# BMS_25.net
KiCad netlist of a schematic drawn in EAGLE
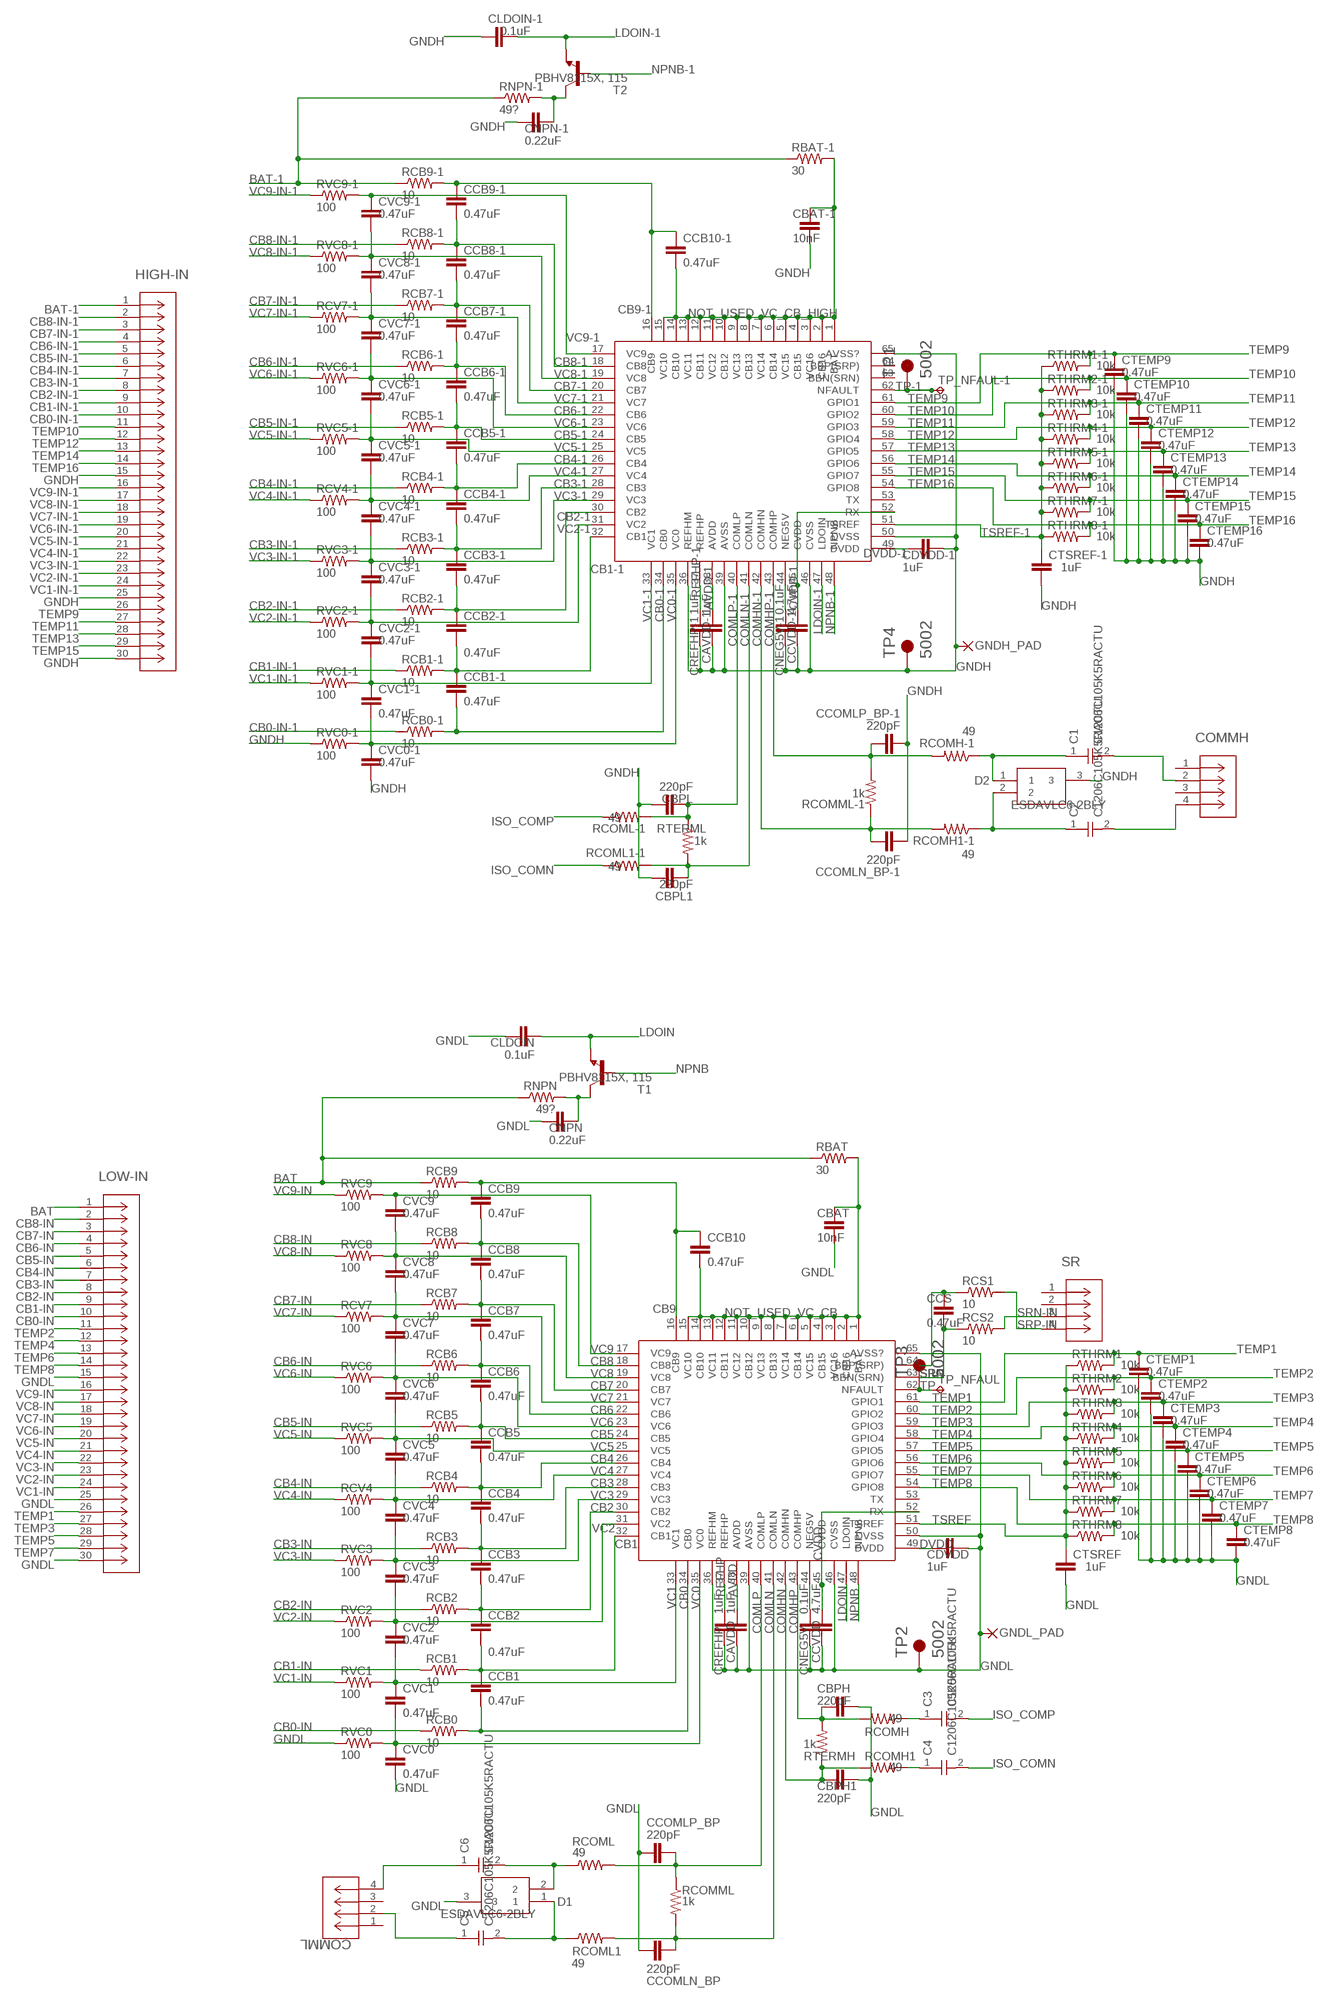
[diagram p0: schematic, sheet 1]

(export (version "E")
  (design (tool "Eeschema 10.0.6"))
  (components
    (comp (ref "C1")
      (value "C1206C105K5RACTU")
      (footprint "eagle-import:CAPC3216X120N")
      (fields (field (name "MF") "KEMET"))
      (libsource (lib "eagle-import") (part "C1206C105K5RACTU"))
    )
    (comp (ref "C2")
      (value "C1206C105K5RACTU")
      (footprint "eagle-import:CAPC3216X120N")
      (fields (field (name "MF") "KEMET"))
      (libsource (lib "eagle-import") (part "C1206C105K5RACTU"))
    )
    (comp (ref "C3")
      (value "C1206C105K5RACTU")
      (footprint "eagle-import:CAPC3216X120N")
      (fields (field (name "MF") "KEMET"))
      (libsource (lib "eagle-import") (part "C1206C105K5RACTU"))
    )
    (comp (ref "C4")
      (value "C1206C105K5RACTU")
      (footprint "eagle-import:CAPC3216X120N")
      (fields (field (name "MF") "KEMET"))
      (libsource (lib "eagle-import") (part "C1206C105K5RACTU"))
    )
    (comp (ref "C5")
      (value "C1206C105K5RACTU")
      (footprint "eagle-import:CAPC3216X120N")
      (fields (field (name "MF") "KEMET"))
      (libsource (lib "eagle-import") (part "C1206C105K5RACTU"))
    )
    (comp (ref "C6")
      (value "C1206C105K5RACTU")
      (footprint "eagle-import:CAPC3216X120N")
      (fields (field (name "MF") "KEMET"))
      (libsource (lib "eagle-import") (part "C1206C105K5RACTU"))
    )
    (comp (ref "CAVDD")
      (value "1uF")
      (footprint "eagle-import:C0603")
      (libsource (lib "eagle-import") (part "CAPACITORC0603"))
    )
    (comp (ref "CAVDD-1")
      (value "1uF")
      (footprint "eagle-import:C0603")
      (libsource (lib "eagle-import") (part "CAPACITORC0603"))
    )
    (comp (ref "CBAT")
      (value "10nF")
      (footprint "eagle-import:C0603")
      (libsource (lib "eagle-import") (part "CAPACITORC0603"))
    )
    (comp (ref "CBAT-1")
      (value "10nF")
      (footprint "eagle-import:C0603")
      (libsource (lib "eagle-import") (part "CAPACITORC0603"))
    )
    (comp (ref "CBPH")
      (value "220pF")
      (footprint "eagle-import:C0603")
      (libsource (lib "eagle-import") (part "CAPACITORC0603"))
    )
    (comp (ref "CBPH1")
      (value "220pF")
      (footprint "eagle-import:C0603")
      (libsource (lib "eagle-import") (part "CAPACITORC0603"))
    )
    (comp (ref "CBPL")
      (value "220pF")
      (footprint "eagle-import:C0603")
      (libsource (lib "eagle-import") (part "CAPACITORC0603"))
    )
    (comp (ref "CBPL1")
      (value "220pF")
      (footprint "eagle-import:C0603")
      (libsource (lib "eagle-import") (part "CAPACITORC0603"))
    )
    (comp (ref "CCB1")
      (value "0.47uF")
      (footprint "eagle-import:C0603")
      (libsource (lib "eagle-import") (part "CAPACITORC0603"))
    )
    (comp (ref "CCB1-1")
      (value "0.47uF")
      (footprint "eagle-import:C0603")
      (libsource (lib "eagle-import") (part "CAPACITORC0603"))
    )
    (comp (ref "CCB2")
      (value "0.47uF")
      (footprint "eagle-import:C0603")
      (libsource (lib "eagle-import") (part "CAPACITORC0603"))
    )
    (comp (ref "CCB2-1")
      (value "0.47uF")
      (footprint "eagle-import:C0603")
      (libsource (lib "eagle-import") (part "CAPACITORC0603"))
    )
    (comp (ref "CCB3")
      (value "0.47uF")
      (footprint "eagle-import:C0603")
      (libsource (lib "eagle-import") (part "CAPACITORC0603"))
    )
    (comp (ref "CCB3-1")
      (value "0.47uF")
      (footprint "eagle-import:C0603")
      (libsource (lib "eagle-import") (part "CAPACITORC0603"))
    )
    (comp (ref "CCB4")
      (value "0.47uF")
      (footprint "eagle-import:C0603")
      (libsource (lib "eagle-import") (part "CAPACITORC0603"))
    )
    (comp (ref "CCB4-1")
      (value "0.47uF")
      (footprint "eagle-import:C0603")
      (libsource (lib "eagle-import") (part "CAPACITORC0603"))
    )
    (comp (ref "CCB5")
      (value "0.47uF")
      (footprint "eagle-import:C0603")
      (libsource (lib "eagle-import") (part "CAPACITORC0603"))
    )
    (comp (ref "CCB5-1")
      (value "0.47uF")
      (footprint "eagle-import:C0603")
      (libsource (lib "eagle-import") (part "CAPACITORC0603"))
    )
    (comp (ref "CCB6")
      (value "0.47uF")
      (footprint "eagle-import:C0603")
      (libsource (lib "eagle-import") (part "CAPACITORC0603"))
    )
    (comp (ref "CCB6-1")
      (value "0.47uF")
      (footprint "eagle-import:C0603")
      (libsource (lib "eagle-import") (part "CAPACITORC0603"))
    )
    (comp (ref "CCB7")
      (value "0.47uF")
      (footprint "eagle-import:C0603")
      (libsource (lib "eagle-import") (part "CAPACITORC0603"))
    )
    (comp (ref "CCB7-1")
      (value "0.47uF")
      (footprint "eagle-import:C0603")
      (libsource (lib "eagle-import") (part "CAPACITORC0603"))
    )
    (comp (ref "CCB8")
      (value "0.47uF")
      (footprint "eagle-import:C0603")
      (libsource (lib "eagle-import") (part "CAPACITORC0603"))
    )
    (comp (ref "CCB8-1")
      (value "0.47uF")
      (footprint "eagle-import:C0603")
      (libsource (lib "eagle-import") (part "CAPACITORC0603"))
    )
    (comp (ref "CCB9")
      (value "0.47uF")
      (footprint "eagle-import:C0603")
      (libsource (lib "eagle-import") (part "CAPACITORC0603"))
    )
    (comp (ref "CCB9-1")
      (value "0.47uF")
      (footprint "eagle-import:C0603")
      (libsource (lib "eagle-import") (part "CAPACITORC0603"))
    )
    (comp (ref "CCB10")
      (value "0.47uF")
      (footprint "eagle-import:C0603")
      (libsource (lib "eagle-import") (part "CAPACITORC0603"))
    )
    (comp (ref "CCB10-1")
      (value "0.47uF")
      (footprint "eagle-import:C0603")
      (libsource (lib "eagle-import") (part "CAPACITORC0603"))
    )
    (comp (ref "CCOMLN_BP")
      (value "220pF")
      (footprint "eagle-import:C0603")
      (libsource (lib "eagle-import") (part "CAPACITORC0603"))
    )
    (comp (ref "CCOMLN_BP-1")
      (value "220pF")
      (footprint "eagle-import:C0603")
      (libsource (lib "eagle-import") (part "CAPACITORC0603"))
    )
    (comp (ref "CCOMLP_BP")
      (value "220pF")
      (footprint "eagle-import:C0603")
      (libsource (lib "eagle-import") (part "CAPACITORC0603"))
    )
    (comp (ref "CCOMLP_BP-1")
      (value "220pF")
      (footprint "eagle-import:C0603")
      (libsource (lib "eagle-import") (part "CAPACITORC0603"))
    )
    (comp (ref "CCS")
      (value "0.47uF")
      (footprint "eagle-import:C0603")
      (libsource (lib "eagle-import") (part "CAPACITORC0603"))
    )
    (comp (ref "CCVDD")
      (value "4.7uF")
      (footprint "eagle-import:C0603")
      (libsource (lib "eagle-import") (part "CAPACITORC0603"))
    )
    (comp (ref "CCVDD-1")
      (value "4.7uF")
      (footprint "eagle-import:C0603")
      (libsource (lib "eagle-import") (part "CAPACITORC0603"))
    )
    (comp (ref "CDVDD")
      (value "1uF")
      (footprint "eagle-import:C0603")
      (libsource (lib "eagle-import") (part "CAPACITORC0603"))
    )
    (comp (ref "CDVDD-1")
      (value "1uF")
      (footprint "eagle-import:C0603")
      (libsource (lib "eagle-import") (part "CAPACITORC0603"))
    )
    (comp (ref "CLDOIN")
      (value "0.1uF")
      (footprint "eagle-import:C0603")
      (libsource (lib "eagle-import") (part "CAPACITORC0603"))
    )
    (comp (ref "CLDOIN-1")
      (value "0.1uF")
      (footprint "eagle-import:C0603")
      (libsource (lib "eagle-import") (part "CAPACITORC0603"))
    )
    (comp (ref "CNEG5V")
      (value "0.1uF")
      (footprint "eagle-import:C0603")
      (libsource (lib "eagle-import") (part "CAPACITORC0603"))
    )
    (comp (ref "CNEG5V-1")
      (value "0.1uF")
      (footprint "eagle-import:C0603")
      (libsource (lib "eagle-import") (part "CAPACITORC0603"))
    )
    (comp (ref "CNPN")
      (value "0.22uF")
      (footprint "eagle-import:C0603")
      (libsource (lib "eagle-import") (part "CAPACITORC0603"))
    )
    (comp (ref "CNPN-1")
      (value "0.22uF")
      (footprint "eagle-import:C0603")
      (libsource (lib "eagle-import") (part "CAPACITORC0603"))
    )
    (comp (ref "COMMH")
      (value "DF11-4DP-2DSA(24)")
      (footprint "eagle-import:CON4_2X2_UF_DF11_HIR")
      (fields (field (name "COPYRIGHT") "Copyright (C) 2023 Ultra Librarian. All rights reserved."))
      (libsource (lib "eagle-import") (part "DF11-4DP-2DSA(24)"))
    )
    (comp (ref "COMML")
      (value "DF11-4DP-2DSA(24)")
      (footprint "eagle-import:CON4_2X2_UF_DF11_HIR")
      (fields (field (name "COPYRIGHT") "Copyright (C) 2023 Ultra Librarian. All rights reserved."))
      (libsource (lib "eagle-import") (part "DF11-4DP-2DSA(24)"))
    )
    (comp (ref "CREFHP")
      (value "1uF")
      (footprint "eagle-import:C0603")
      (libsource (lib "eagle-import") (part "CAPACITORC0603"))
    )
    (comp (ref "CREFHP-1")
      (value "1uF")
      (footprint "eagle-import:C0603")
      (libsource (lib "eagle-import") (part "CAPACITORC0603"))
    )
    (comp (ref "CTEMP1")
      (value "0.47uF")
      (footprint "eagle-import:C0603")
      (libsource (lib "eagle-import") (part "CAPACITORC0603"))
    )
    (comp (ref "CTEMP2")
      (value "0.47uF")
      (footprint "eagle-import:C0603")
      (libsource (lib "eagle-import") (part "CAPACITORC0603"))
    )
    (comp (ref "CTEMP3")
      (value "0.47uF")
      (footprint "eagle-import:C0603")
      (libsource (lib "eagle-import") (part "CAPACITORC0603"))
    )
    (comp (ref "CTEMP4")
      (value "0.47uF")
      (footprint "eagle-import:C0603")
      (libsource (lib "eagle-import") (part "CAPACITORC0603"))
    )
    (comp (ref "CTEMP5")
      (value "0.47uF")
      (footprint "eagle-import:C0603")
      (libsource (lib "eagle-import") (part "CAPACITORC0603"))
    )
    (comp (ref "CTEMP6")
      (value "0.47uF")
      (footprint "eagle-import:C0603")
      (libsource (lib "eagle-import") (part "CAPACITORC0603"))
    )
    (comp (ref "CTEMP7")
      (value "0.47uF")
      (footprint "eagle-import:C0603")
      (libsource (lib "eagle-import") (part "CAPACITORC0603"))
    )
    (comp (ref "CTEMP8")
      (value "0.47uF")
      (footprint "eagle-import:C0603")
      (libsource (lib "eagle-import") (part "CAPACITORC0603"))
    )
    (comp (ref "CTEMP9")
      (value "0.47uF")
      (footprint "eagle-import:C0603")
      (libsource (lib "eagle-import") (part "CAPACITORC0603"))
    )
    (comp (ref "CTEMP10")
      (value "0.47uF")
      (footprint "eagle-import:C0603")
      (libsource (lib "eagle-import") (part "CAPACITORC0603"))
    )
    (comp (ref "CTEMP11")
      (value "0.47uF")
      (footprint "eagle-import:C0603")
      (libsource (lib "eagle-import") (part "CAPACITORC0603"))
    )
    (comp (ref "CTEMP12")
      (value "0.47uF")
      (footprint "eagle-import:C0603")
      (libsource (lib "eagle-import") (part "CAPACITORC0603"))
    )
    (comp (ref "CTEMP13")
      (value "0.47uF")
      (footprint "eagle-import:C0603")
      (libsource (lib "eagle-import") (part "CAPACITORC0603"))
    )
    (comp (ref "CTEMP14")
      (value "0.47uF")
      (footprint "eagle-import:C0603")
      (libsource (lib "eagle-import") (part "CAPACITORC0603"))
    )
    (comp (ref "CTEMP15")
      (value "0.47uF")
      (footprint "eagle-import:C0603")
      (libsource (lib "eagle-import") (part "CAPACITORC0603"))
    )
    (comp (ref "CTEMP16")
      (value "0.47uF")
      (footprint "eagle-import:C0603")
      (libsource (lib "eagle-import") (part "CAPACITORC0603"))
    )
    (comp (ref "CTSREF")
      (value "1uF")
      (footprint "eagle-import:C0603")
      (libsource (lib "eagle-import") (part "CAPACITORC0603"))
    )
    (comp (ref "CTSREF-1")
      (value "1uF")
      (footprint "eagle-import:C0603")
      (libsource (lib "eagle-import") (part "CAPACITORC0603"))
    )
    (comp (ref "CVC0")
      (value "0.47uF")
      (footprint "eagle-import:C0603")
      (libsource (lib "eagle-import") (part "CAPACITORC0603"))
    )
    (comp (ref "CVC0-1")
      (value "0.47uF")
      (footprint "eagle-import:C0603")
      (libsource (lib "eagle-import") (part "CAPACITORC0603"))
    )
    (comp (ref "CVC1")
      (value "0.47uF")
      (footprint "eagle-import:C0603")
      (libsource (lib "eagle-import") (part "CAPACITORC0603"))
    )
    (comp (ref "CVC1-1")
      (value "0.47uF")
      (footprint "eagle-import:C0603")
      (libsource (lib "eagle-import") (part "CAPACITORC0603"))
    )
    (comp (ref "CVC2")
      (value "0.47uF")
      (footprint "eagle-import:C0603")
      (libsource (lib "eagle-import") (part "CAPACITORC0603"))
    )
    (comp (ref "CVC2-1")
      (value "0.47uF")
      (footprint "eagle-import:C0603")
      (libsource (lib "eagle-import") (part "CAPACITORC0603"))
    )
    (comp (ref "CVC3")
      (value "0.47uF")
      (footprint "eagle-import:C0603")
      (libsource (lib "eagle-import") (part "CAPACITORC0603"))
    )
    (comp (ref "CVC3-1")
      (value "0.47uF")
      (footprint "eagle-import:C0603")
      (libsource (lib "eagle-import") (part "CAPACITORC0603"))
    )
    (comp (ref "CVC4")
      (value "0.47uF")
      (footprint "eagle-import:C0603")
      (libsource (lib "eagle-import") (part "CAPACITORC0603"))
    )
    (comp (ref "CVC4-1")
      (value "0.47uF")
      (footprint "eagle-import:C0603")
      (libsource (lib "eagle-import") (part "CAPACITORC0603"))
    )
    (comp (ref "CVC5")
      (value "0.47uF")
      (footprint "eagle-import:C0603")
      (libsource (lib "eagle-import") (part "CAPACITORC0603"))
    )
    (comp (ref "CVC5-1")
      (value "0.47uF")
      (footprint "eagle-import:C0603")
      (libsource (lib "eagle-import") (part "CAPACITORC0603"))
    )
    (comp (ref "CVC6")
      (value "0.47uF")
      (footprint "eagle-import:C0603")
      (libsource (lib "eagle-import") (part "CAPACITORC0603"))
    )
    (comp (ref "CVC6-1")
      (value "0.47uF")
      (footprint "eagle-import:C0603")
      (libsource (lib "eagle-import") (part "CAPACITORC0603"))
    )
    (comp (ref "CVC7")
      (value "0.47uF")
      (footprint "eagle-import:C0603")
      (libsource (lib "eagle-import") (part "CAPACITORC0603"))
    )
    (comp (ref "CVC7-1")
      (value "0.47uF")
      (footprint "eagle-import:C0603")
      (libsource (lib "eagle-import") (part "CAPACITORC0603"))
    )
    (comp (ref "CVC8")
      (value "0.47uF")
      (footprint "eagle-import:C0603")
      (libsource (lib "eagle-import") (part "CAPACITORC0603"))
    )
    (comp (ref "CVC8-1")
      (value "0.47uF")
      (footprint "eagle-import:C0603")
      (libsource (lib "eagle-import") (part "CAPACITORC0603"))
    )
    (comp (ref "CVC9")
      (value "0.47uF")
      (footprint "eagle-import:C0603")
      (libsource (lib "eagle-import") (part "CAPACITORC0603"))
    )
    (comp (ref "CVC9-1")
      (value "0.47uF")
      (footprint "eagle-import:C0603")
      (libsource (lib "eagle-import") (part "CAPACITORC0603"))
    )
    (comp (ref "D1")
      (value "ESDAVLC6-2BLY")
      (footprint "eagle-import:SOT95P255X150-3N")
      (fields (field (name "MOUSER_PART_NUMBER") "511-ESDAVLC6-2BLY"))
      (libsource (lib "eagle-import") (part "ESDAVLC6-2BLY"))
    )
    (comp (ref "D2")
      (value "ESDAVLC6-2BLY")
      (footprint "eagle-import:SOT95P255X150-3N")
      (fields (field (name "MOUSER_PART_NUMBER") "511-ESDAVLC6-2BLY"))
      (libsource (lib "eagle-import") (part "ESDAVLC6-2BLY"))
    )
    (comp (ref "GNDH_PAD")
      (value "SMD2")
      (footprint "eagle-import:SMD1,27-2,54")
      (libsource (lib "eagle-import") (part "SMD2"))
    )
    (comp (ref "GNDL_PAD")
      (value "SMD2")
      (footprint "eagle-import:SMD1,27-2,54")
      (libsource (lib "eagle-import") (part "SMD2"))
    )
    (comp (ref "HIGH-IN")
      (value "87606-315LF")
      (footprint "eagle-import:87606-315LF_AMP")
      (fields (field (name "COPYRIGHT") "Copyright (C) 2024 Ultra Librarian. All rights reserved."))
      (libsource (lib "eagle-import") (part "87606-315LF"))
    )
    (comp (ref "IC1")
      (value "PBQ79656PAPTQ1")
      (footprint "eagle-import:QFP50P1200X1200X120-65N")
      (libsource (lib "eagle-import") (part "PBQ79656PAPTQ1"))
    )
    (comp (ref "IC2")
      (value "PBQ79656PAPTQ1")
      (footprint "eagle-import:QFP50P1200X1200X120-65N")
      (libsource (lib "eagle-import") (part "PBQ79656PAPTQ1"))
    )
    (comp (ref "LOW-IN")
      (value "87606-315LF")
      (footprint "eagle-import:87606-315LF_AMP")
      (fields (field (name "COPYRIGHT") "Copyright (C) 2024 Ultra Librarian. All rights reserved."))
      (libsource (lib "eagle-import") (part "87606-315LF"))
    )
    (comp (ref "RBAT")
      (value "30")
      (footprint "eagle-import:R0603")
      (libsource (lib "eagle-import") (part "RESISTORR0603"))
    )
    (comp (ref "RBAT-1")
      (value "30")
      (footprint "eagle-import:R0603")
      (libsource (lib "eagle-import") (part "RESISTORR0603"))
    )
    (comp (ref "RCB0")
      (value "10")
      (footprint "eagle-import:R2010")
      (libsource (lib "eagle-import") (part "R-US_R2010"))
    )
    (comp (ref "RCB0-1")
      (value "10")
      (footprint "eagle-import:R2010")
      (libsource (lib "eagle-import") (part "R-US_R2010"))
    )
    (comp (ref "RCB1")
      (value "10")
      (footprint "eagle-import:R2010")
      (libsource (lib "eagle-import") (part "R-US_R2010"))
    )
    (comp (ref "RCB1-1")
      (value "10")
      (footprint "eagle-import:R2010")
      (libsource (lib "eagle-import") (part "R-US_R2010"))
    )
    (comp (ref "RCB2")
      (value "10")
      (footprint "eagle-import:R2010")
      (libsource (lib "eagle-import") (part "R-US_R2010"))
    )
    (comp (ref "RCB2-1")
      (value "10")
      (footprint "eagle-import:R2010")
      (libsource (lib "eagle-import") (part "R-US_R2010"))
    )
    (comp (ref "RCB3")
      (value "10")
      (footprint "eagle-import:R2010")
      (libsource (lib "eagle-import") (part "R-US_R2010"))
    )
    (comp (ref "RCB3-1")
      (value "10")
      (footprint "eagle-import:R2010")
      (libsource (lib "eagle-import") (part "R-US_R2010"))
    )
    (comp (ref "RCB4")
      (value "10")
      (footprint "eagle-import:R2010")
      (libsource (lib "eagle-import") (part "R-US_R2010"))
    )
    (comp (ref "RCB4-1")
      (value "10")
      (footprint "eagle-import:R2010")
      (libsource (lib "eagle-import") (part "R-US_R2010"))
    )
    (comp (ref "RCB5")
      (value "10")
      (footprint "eagle-import:R2010")
      (libsource (lib "eagle-import") (part "R-US_R2010"))
    )
    (comp (ref "RCB5-1")
      (value "10")
      (footprint "eagle-import:R2010")
      (libsource (lib "eagle-import") (part "R-US_R2010"))
    )
    (comp (ref "RCB6")
      (value "10")
      (footprint "eagle-import:R2010")
      (libsource (lib "eagle-import") (part "R-US_R2010"))
    )
    (comp (ref "RCB6-1")
      (value "10")
      (footprint "eagle-import:R2010")
      (libsource (lib "eagle-import") (part "R-US_R2010"))
    )
    (comp (ref "RCB7")
      (value "10")
      (footprint "eagle-import:R2010")
      (libsource (lib "eagle-import") (part "R-US_R2010"))
    )
    (comp (ref "RCB7-1")
      (value "10")
      (footprint "eagle-import:R2010")
      (libsource (lib "eagle-import") (part "R-US_R2010"))
    )
    (comp (ref "RCB8")
      (value "10")
      (footprint "eagle-import:R2010")
      (libsource (lib "eagle-import") (part "R-US_R2010"))
    )
    (comp (ref "RCB8-1")
      (value "10")
      (footprint "eagle-import:R2010")
      (libsource (lib "eagle-import") (part "R-US_R2010"))
    )
    (comp (ref "RCB9")
      (value "10")
      (footprint "eagle-import:R2010")
      (libsource (lib "eagle-import") (part "R-US_R2010"))
    )
    (comp (ref "RCB9-1")
      (value "10")
      (footprint "eagle-import:R2010")
      (libsource (lib "eagle-import") (part "R-US_R2010"))
    )
    (comp (ref "RCOMH")
      (value "49")
      (footprint "eagle-import:R0603")
      (libsource (lib "eagle-import") (part "RESISTORR0603"))
    )
    (comp (ref "RCOMH-1")
      (value "49")
      (footprint "eagle-import:R0603")
      (libsource (lib "eagle-import") (part "RESISTORR0603"))
    )
    (comp (ref "RCOMH1")
      (value "49")
      (footprint "eagle-import:R0603")
      (libsource (lib "eagle-import") (part "RESISTORR0603"))
    )
    (comp (ref "RCOMH1-1")
      (value "49")
      (footprint "eagle-import:R0603")
      (libsource (lib "eagle-import") (part "RESISTORR0603"))
    )
    (comp (ref "RCOML")
      (value "49")
      (footprint "eagle-import:R0603")
      (libsource (lib "eagle-import") (part "RESISTORR0603"))
    )
    (comp (ref "RCOML-1")
      (value "49")
      (footprint "eagle-import:R0603")
      (libsource (lib "eagle-import") (part "RESISTORR0603"))
    )
    (comp (ref "RCOML1")
      (value "49")
      (footprint "eagle-import:R0603")
      (libsource (lib "eagle-import") (part "RESISTORR0603"))
    )
    (comp (ref "RCOML1-1")
      (value "49")
      (footprint "eagle-import:R0603")
      (libsource (lib "eagle-import") (part "RESISTORR0603"))
    )
    (comp (ref "RCOMML")
      (value "1k")
      (footprint "eagle-import:R0603")
      (libsource (lib "eagle-import") (part "RESISTORR0603"))
    )
    (comp (ref "RCOMML-1")
      (value "1k")
      (footprint "eagle-import:R0603")
      (libsource (lib "eagle-import") (part "RESISTORR0603"))
    )
    (comp (ref "RCS1")
      (value "10")
      (footprint "eagle-import:R0603")
      (libsource (lib "eagle-import") (part "RESISTORR0603"))
    )
    (comp (ref "RCS2")
      (value "10")
      (footprint "eagle-import:R0603")
      (libsource (lib "eagle-import") (part "RESISTORR0603"))
    )
    (comp (ref "RCV4")
      (value "100")
      (footprint "eagle-import:R0603")
      (libsource (lib "eagle-import") (part "RESISTORR0603"))
    )
    (comp (ref "RCV4-1")
      (value "100")
      (footprint "eagle-import:R0603")
      (libsource (lib "eagle-import") (part "RESISTORR0603"))
    )
    (comp (ref "RCV7")
      (value "100")
      (footprint "eagle-import:R0603")
      (libsource (lib "eagle-import") (part "RESISTORR0603"))
    )
    (comp (ref "RCV7-1")
      (value "100")
      (footprint "eagle-import:R0603")
      (libsource (lib "eagle-import") (part "RESISTORR0603"))
    )
    (comp (ref "RNPN")
      (value "49?")
      (footprint "eagle-import:R0603")
      (libsource (lib "eagle-import") (part "RESISTORR0603"))
    )
    (comp (ref "RNPN-1")
      (value "49?")
      (footprint "eagle-import:R0603")
      (libsource (lib "eagle-import") (part "RESISTORR0603"))
    )
    (comp (ref "RTERMH")
      (value "1k")
      (footprint "eagle-import:R0603")
      (libsource (lib "eagle-import") (part "RESISTORR0603"))
    )
    (comp (ref "RTERML")
      (value "1k")
      (footprint "eagle-import:R0603")
      (libsource (lib "eagle-import") (part "RESISTORR0603"))
    )
    (comp (ref "RTHRM1")
      (value "10k")
      (footprint "eagle-import:R0603")
      (libsource (lib "eagle-import") (part "RESISTORR0603"))
    )
    (comp (ref "RTHRM1-1")
      (value "10k")
      (footprint "eagle-import:R0603")
      (libsource (lib "eagle-import") (part "RESISTORR0603"))
    )
    (comp (ref "RTHRM2")
      (value "10k")
      (footprint "eagle-import:R0603")
      (libsource (lib "eagle-import") (part "RESISTORR0603"))
    )
    (comp (ref "RTHRM2-1")
      (value "10k")
      (footprint "eagle-import:R0603")
      (libsource (lib "eagle-import") (part "RESISTORR0603"))
    )
    (comp (ref "RTHRM3")
      (value "10k")
      (footprint "eagle-import:R0603")
      (libsource (lib "eagle-import") (part "RESISTORR0603"))
    )
    (comp (ref "RTHRM3-1")
      (value "10k")
      (footprint "eagle-import:R0603")
      (libsource (lib "eagle-import") (part "RESISTORR0603"))
    )
    (comp (ref "RTHRM4")
      (value "10k")
      (footprint "eagle-import:R0603")
      (libsource (lib "eagle-import") (part "RESISTORR0603"))
    )
    (comp (ref "RTHRM4-1")
      (value "10k")
      (footprint "eagle-import:R0603")
      (libsource (lib "eagle-import") (part "RESISTORR0603"))
    )
    (comp (ref "RTHRM5")
      (value "10k")
      (footprint "eagle-import:R0603")
      (libsource (lib "eagle-import") (part "RESISTORR0603"))
    )
    (comp (ref "RTHRM5-1")
      (value "10k")
      (footprint "eagle-import:R0603")
      (libsource (lib "eagle-import") (part "RESISTORR0603"))
    )
    (comp (ref "RTHRM6")
      (value "10k")
      (footprint "eagle-import:R0603")
      (libsource (lib "eagle-import") (part "RESISTORR0603"))
    )
    (comp (ref "RTHRM6-1")
      (value "10k")
      (footprint "eagle-import:R0603")
      (libsource (lib "eagle-import") (part "RESISTORR0603"))
    )
    (comp (ref "RTHRM7")
      (value "10k")
      (footprint "eagle-import:R0603")
      (libsource (lib "eagle-import") (part "RESISTORR0603"))
    )
    (comp (ref "RTHRM7-1")
      (value "10k")
      (footprint "eagle-import:R0603")
      (libsource (lib "eagle-import") (part "RESISTORR0603"))
    )
    (comp (ref "RTHRM8")
      (value "10k")
      (footprint "eagle-import:R0603")
      (libsource (lib "eagle-import") (part "RESISTORR0603"))
    )
    (comp (ref "RTHRM8-1")
      (value "10k")
      (footprint "eagle-import:R0603")
      (libsource (lib "eagle-import") (part "RESISTORR0603"))
    )
    (comp (ref "RVC0")
      (value "100")
      (footprint "eagle-import:R0603")
      (libsource (lib "eagle-import") (part "RESISTORR0603"))
    )
    (comp (ref "RVC0-1")
      (value "100")
      (footprint "eagle-import:R0603")
      (libsource (lib "eagle-import") (part "RESISTORR0603"))
    )
    (comp (ref "RVC1")
      (value "100")
      (footprint "eagle-import:R0603")
      (libsource (lib "eagle-import") (part "RESISTORR0603"))
    )
    (comp (ref "RVC1-1")
      (value "100")
      (footprint "eagle-import:R0603")
      (libsource (lib "eagle-import") (part "RESISTORR0603"))
    )
    (comp (ref "RVC2")
      (value "100")
      (footprint "eagle-import:R0603")
      (libsource (lib "eagle-import") (part "RESISTORR0603"))
    )
    (comp (ref "RVC2-1")
      (value "100")
      (footprint "eagle-import:R0603")
      (libsource (lib "eagle-import") (part "RESISTORR0603"))
    )
    (comp (ref "RVC3")
      (value "100")
      (footprint "eagle-import:R0603")
      (libsource (lib "eagle-import") (part "RESISTORR0603"))
    )
    (comp (ref "RVC3-1")
      (value "100")
      (footprint "eagle-import:R0603")
      (libsource (lib "eagle-import") (part "RESISTORR0603"))
    )
    (comp (ref "RVC5")
      (value "100")
      (footprint "eagle-import:R0603")
      (libsource (lib "eagle-import") (part "RESISTORR0603"))
    )
    (comp (ref "RVC5-1")
      (value "100")
      (footprint "eagle-import:R0603")
      (libsource (lib "eagle-import") (part "RESISTORR0603"))
    )
    (comp (ref "RVC6")
      (value "100")
      (footprint "eagle-import:R0603")
      (libsource (lib "eagle-import") (part "RESISTORR0603"))
    )
    (comp (ref "RVC6-1")
      (value "100")
      (footprint "eagle-import:R0603")
      (libsource (lib "eagle-import") (part "RESISTORR0603"))
    )
    (comp (ref "RVC8")
      (value "100")
      (footprint "eagle-import:R0603")
      (libsource (lib "eagle-import") (part "RESISTORR0603"))
    )
    (comp (ref "RVC8-1")
      (value "100")
      (footprint "eagle-import:R0603")
      (libsource (lib "eagle-import") (part "RESISTORR0603"))
    )
    (comp (ref "RVC9")
      (value "100")
      (footprint "eagle-import:R0603")
      (libsource (lib "eagle-import") (part "RESISTORR0603"))
    )
    (comp (ref "RVC9-1")
      (value "100")
      (footprint "eagle-import:R0603")
      (libsource (lib "eagle-import") (part "RESISTORR0603"))
    )
    (comp (ref "SR")
      (value "DF11-4DP-2DSA(24)")
      (footprint "eagle-import:CON4_2X2_UF_DF11_HIR")
      (fields (field (name "COPYRIGHT") "Copyright (C) 2023 Ultra Librarian. All rights reserved."))
      (libsource (lib "eagle-import") (part "DF11-4DP-2DSA(24)"))
    )
    (comp (ref "T1")
      (value "PBHV8115X, 115")
      (footprint "eagle-import:SOT89-BCE")
      (libsource (lib "eagle-import") (part "-NPN-SOT89-BCEBC868"))
    )
    (comp (ref "T2")
      (value "PBHV8115X, 115")
      (footprint "eagle-import:SOT89-BCE")
      (libsource (lib "eagle-import") (part "-NPN-SOT89-BCEBC868"))
    )
    (comp (ref "TP1")
      (value "5002")
      (footprint "eagle-import:KEYSTONE_5002")
      (fields (field (name "MANUFACTURER") "Keystone"))
      (libsource (lib "eagle-import") (part "5002"))
    )
    (comp (ref "TP2")
      (value "5002")
      (footprint "eagle-import:KEYSTONE_5002")
      (fields (field (name "MANUFACTURER") "Keystone"))
      (libsource (lib "eagle-import") (part "5002"))
    )
    (comp (ref "TP3")
      (value "5002")
      (footprint "eagle-import:KEYSTONE_5002")
      (fields (field (name "MANUFACTURER") "Keystone"))
      (libsource (lib "eagle-import") (part "5002"))
    )
    (comp (ref "TP4")
      (value "5002")
      (footprint "eagle-import:KEYSTONE_5002")
      (fields (field (name "MANUFACTURER") "Keystone"))
      (libsource (lib "eagle-import") (part "5002"))
    )
    (comp (ref "TP_NFAUL")
      (value "TPB2,54")
      (footprint "eagle-import:B2,54")
      (libsource (lib "eagle-import") (part "TPB2,54"))
    )
    (comp (ref "TP_NFAUL-1")
      (value "TPB2,54")
      (footprint "eagle-import:B2,54")
      (libsource (lib "eagle-import") (part "TPB2,54"))
    )
  )
  (nets
    (net (code "1") (name "/AVDD") (class "Default")
      (node (ref "CAVDD") (pin "1") (pinfunction "1_1") (pintype "passive"))
      (node (ref "IC2") (pin "38") (pinfunction "AVDD_38") (pintype "bidirectional"))
    )
    (net (code "2") (name "/AVDD-1") (class "Default")
      (node (ref "CAVDD-1") (pin "1") (pinfunction "1_1") (pintype "passive"))
      (node (ref "IC1") (pin "38") (pinfunction "AVDD_38") (pintype "bidirectional"))
    )
    (net (code "3") (name "/BAT") (class "Default")
      (node (ref "LOW-IN") (pin "1") (pinfunction "1_1") (pintype "passive"))
      (node (ref "RBAT") (pin "1") (pinfunction "1_1") (pintype "passive"))
      (node (ref "RCB9") (pin "1") (pinfunction "1_1") (pintype "passive"))
      (node (ref "RNPN") (pin "1") (pinfunction "1_1") (pintype "passive"))
    )
    (net (code "4") (name "/BAT-1") (class "Default")
      (node (ref "HIGH-IN") (pin "1") (pinfunction "1_1") (pintype "passive"))
      (node (ref "RBAT-1") (pin "1") (pinfunction "1_1") (pintype "passive"))
      (node (ref "RCB9-1") (pin "1") (pinfunction "1_1") (pintype "passive"))
      (node (ref "RNPN-1") (pin "1") (pinfunction "1_1") (pintype "passive"))
    )
    (net (code "5") (name "/CB0") (class "Default")
      (node (ref "CCB1") (pin "2") (pinfunction "2_2") (pintype "passive"))
      (node (ref "IC2") (pin "34") (pinfunction "CB0_34") (pintype "bidirectional"))
      (node (ref "RCB0") (pin "2") (pinfunction "2_2") (pintype "passive"))
    )
    (net (code "6") (name "/CB0-1") (class "Default")
      (node (ref "CCB1-1") (pin "2") (pinfunction "2_2") (pintype "passive"))
      (node (ref "IC1") (pin "34") (pinfunction "CB0_34") (pintype "bidirectional"))
      (node (ref "RCB0-1") (pin "2") (pinfunction "2_2") (pintype "passive"))
    )
    (net (code "7") (name "/CB0-IN") (class "Default")
      (node (ref "LOW-IN") (pin "10") (pinfunction "10_10") (pintype "passive"))
      (node (ref "RCB0") (pin "1") (pinfunction "1_1") (pintype "passive"))
    )
    (net (code "8") (name "/CB0-IN-1") (class "Default")
      (node (ref "HIGH-IN") (pin "10") (pinfunction "10_10") (pintype "passive"))
      (node (ref "RCB0-1") (pin "1") (pinfunction "1_1") (pintype "passive"))
    )
    (net (code "9") (name "/CB1") (class "Default")
      (node (ref "CCB1") (pin "1") (pinfunction "1_1") (pintype "passive"))
      (node (ref "CCB2") (pin "2") (pinfunction "2_2") (pintype "passive"))
      (node (ref "IC2") (pin "32") (pinfunction "CB1_32") (pintype "bidirectional"))
      (node (ref "RCB1") (pin "2") (pinfunction "2_2") (pintype "passive"))
    )
    (net (code "10") (name "/CB1-1") (class "Default")
      (node (ref "CCB1-1") (pin "1") (pinfunction "1_1") (pintype "passive"))
      (node (ref "CCB2-1") (pin "2") (pinfunction "2_2") (pintype "passive"))
      (node (ref "IC1") (pin "32") (pinfunction "CB1_32") (pintype "bidirectional"))
      (node (ref "RCB1-1") (pin "2") (pinfunction "2_2") (pintype "passive"))
    )
    (net (code "11") (name "/CB1-IN") (class "Default")
      (node (ref "LOW-IN") (pin "9") (pinfunction "9_9") (pintype "passive"))
      (node (ref "RCB1") (pin "1") (pinfunction "1_1") (pintype "passive"))
    )
    (net (code "12") (name "/CB1-IN-1") (class "Default")
      (node (ref "HIGH-IN") (pin "9") (pinfunction "9_9") (pintype "passive"))
      (node (ref "RCB1-1") (pin "1") (pinfunction "1_1") (pintype "passive"))
    )
    (net (code "13") (name "/CB2") (class "Default")
      (node (ref "CCB2") (pin "1") (pinfunction "1_1") (pintype "passive"))
      (node (ref "CCB3") (pin "2") (pinfunction "2_2") (pintype "passive"))
      (node (ref "IC2") (pin "30") (pinfunction "CB2_30") (pintype "bidirectional"))
      (node (ref "RCB2") (pin "2") (pinfunction "2_2") (pintype "passive"))
    )
    (net (code "14") (name "/CB2-1") (class "Default")
      (node (ref "CCB2-1") (pin "1") (pinfunction "1_1") (pintype "passive"))
      (node (ref "CCB3-1") (pin "2") (pinfunction "2_2") (pintype "passive"))
      (node (ref "IC1") (pin "30") (pinfunction "CB2_30") (pintype "bidirectional"))
      (node (ref "RCB2-1") (pin "2") (pinfunction "2_2") (pintype "passive"))
    )
    (net (code "15") (name "/CB2-IN") (class "Default")
      (node (ref "LOW-IN") (pin "8") (pinfunction "8_8") (pintype "passive"))
      (node (ref "RCB2") (pin "1") (pinfunction "1_1") (pintype "passive"))
    )
    (net (code "16") (name "/CB2-IN-1") (class "Default")
      (node (ref "HIGH-IN") (pin "8") (pinfunction "8_8") (pintype "passive"))
      (node (ref "RCB2-1") (pin "1") (pinfunction "1_1") (pintype "passive"))
    )
    (net (code "17") (name "/CB3") (class "Default")
      (node (ref "CCB3") (pin "1") (pinfunction "1_1") (pintype "passive"))
      (node (ref "CCB4") (pin "2") (pinfunction "2_2") (pintype "passive"))
      (node (ref "IC2") (pin "28") (pinfunction "CB3_28") (pintype "bidirectional"))
      (node (ref "RCB3") (pin "2") (pinfunction "2_2") (pintype "passive"))
    )
    (net (code "18") (name "/CB3-1") (class "Default")
      (node (ref "CCB3-1") (pin "1") (pinfunction "1_1") (pintype "passive"))
      (node (ref "CCB4-1") (pin "2") (pinfunction "2_2") (pintype "passive"))
      (node (ref "IC1") (pin "28") (pinfunction "CB3_28") (pintype "bidirectional"))
      (node (ref "RCB3-1") (pin "2") (pinfunction "2_2") (pintype "passive"))
    )
    (net (code "19") (name "/CB3-IN") (class "Default")
      (node (ref "LOW-IN") (pin "7") (pinfunction "7_7") (pintype "passive"))
      (node (ref "RCB3") (pin "1") (pinfunction "1_1") (pintype "passive"))
    )
    (net (code "20") (name "/CB3-IN-1") (class "Default")
      (node (ref "HIGH-IN") (pin "7") (pinfunction "7_7") (pintype "passive"))
      (node (ref "RCB3-1") (pin "1") (pinfunction "1_1") (pintype "passive"))
    )
    (net (code "21") (name "/CB4") (class "Default")
      (node (ref "CCB4") (pin "1") (pinfunction "1_1") (pintype "passive"))
      (node (ref "CCB5") (pin "2") (pinfunction "2_2") (pintype "passive"))
      (node (ref "IC2") (pin "26") (pinfunction "CB4_26") (pintype "bidirectional"))
      (node (ref "RCB4") (pin "2") (pinfunction "2_2") (pintype "passive"))
    )
    (net (code "22") (name "/CB4-1") (class "Default")
      (node (ref "CCB4-1") (pin "1") (pinfunction "1_1") (pintype "passive"))
      (node (ref "CCB5-1") (pin "2") (pinfunction "2_2") (pintype "passive"))
      (node (ref "IC1") (pin "26") (pinfunction "CB4_26") (pintype "bidirectional"))
      (node (ref "RCB4-1") (pin "2") (pinfunction "2_2") (pintype "passive"))
    )
    (net (code "23") (name "/CB4-IN") (class "Default")
      (node (ref "LOW-IN") (pin "6") (pinfunction "6_6") (pintype "passive"))
      (node (ref "RCB4") (pin "1") (pinfunction "1_1") (pintype "passive"))
    )
    (net (code "24") (name "/CB4-IN-1") (class "Default")
      (node (ref "HIGH-IN") (pin "6") (pinfunction "6_6") (pintype "passive"))
      (node (ref "RCB4-1") (pin "1") (pinfunction "1_1") (pintype "passive"))
    )
    (net (code "25") (name "/CB5") (class "Default")
      (node (ref "CCB5") (pin "1") (pinfunction "1_1") (pintype "passive"))
      (node (ref "CCB6") (pin "2") (pinfunction "2_2") (pintype "passive"))
      (node (ref "IC2") (pin "24") (pinfunction "CB5_24") (pintype "bidirectional"))
      (node (ref "RCB5") (pin "2") (pinfunction "2_2") (pintype "passive"))
    )
    (net (code "26") (name "/CB5-1") (class "Default")
      (node (ref "CCB5-1") (pin "1") (pinfunction "1_1") (pintype "passive"))
      (node (ref "CCB6-1") (pin "2") (pinfunction "2_2") (pintype "passive"))
      (node (ref "IC1") (pin "24") (pinfunction "CB5_24") (pintype "bidirectional"))
      (node (ref "RCB5-1") (pin "2") (pinfunction "2_2") (pintype "passive"))
    )
    (net (code "27") (name "/CB5-IN") (class "Default")
      (node (ref "LOW-IN") (pin "5") (pinfunction "5_5") (pintype "passive"))
      (node (ref "RCB5") (pin "1") (pinfunction "1_1") (pintype "passive"))
    )
    (net (code "28") (name "/CB5-IN-1") (class "Default")
      (node (ref "HIGH-IN") (pin "5") (pinfunction "5_5") (pintype "passive"))
      (node (ref "RCB5-1") (pin "1") (pinfunction "1_1") (pintype "passive"))
    )
    (net (code "29") (name "/CB6") (class "Default")
      (node (ref "CCB6") (pin "1") (pinfunction "1_1") (pintype "passive"))
      (node (ref "CCB7") (pin "2") (pinfunction "2_2") (pintype "passive"))
      (node (ref "IC2") (pin "22") (pinfunction "CB6_22") (pintype "bidirectional"))
      (node (ref "RCB6") (pin "2") (pinfunction "2_2") (pintype "passive"))
    )
    (net (code "30") (name "/CB6-1") (class "Default")
      (node (ref "CCB6-1") (pin "1") (pinfunction "1_1") (pintype "passive"))
      (node (ref "CCB7-1") (pin "2") (pinfunction "2_2") (pintype "passive"))
      (node (ref "IC1") (pin "22") (pinfunction "CB6_22") (pintype "bidirectional"))
      (node (ref "RCB6-1") (pin "2") (pinfunction "2_2") (pintype "passive"))
    )
    (net (code "31") (name "/CB6-IN") (class "Default")
      (node (ref "LOW-IN") (pin "4") (pinfunction "4_4") (pintype "passive"))
      (node (ref "RCB6") (pin "1") (pinfunction "1_1") (pintype "passive"))
    )
    (net (code "32") (name "/CB6-IN-1") (class "Default")
      (node (ref "HIGH-IN") (pin "4") (pinfunction "4_4") (pintype "passive"))
      (node (ref "RCB6-1") (pin "1") (pinfunction "1_1") (pintype "passive"))
    )
    (net (code "33") (name "/CB7") (class "Default")
      (node (ref "CCB7") (pin "1") (pinfunction "1_1") (pintype "passive"))
      (node (ref "CCB8") (pin "2") (pinfunction "2_2") (pintype "passive"))
      (node (ref "IC2") (pin "20") (pinfunction "CB7_20") (pintype "bidirectional"))
      (node (ref "RCB7") (pin "2") (pinfunction "2_2") (pintype "passive"))
    )
    (net (code "34") (name "/CB7-1") (class "Default")
      (node (ref "CCB7-1") (pin "1") (pinfunction "1_1") (pintype "passive"))
      (node (ref "CCB8-1") (pin "2") (pinfunction "2_2") (pintype "passive"))
      (node (ref "IC1") (pin "20") (pinfunction "CB7_20") (pintype "bidirectional"))
      (node (ref "RCB7-1") (pin "2") (pinfunction "2_2") (pintype "passive"))
    )
    (net (code "35") (name "/CB7-IN") (class "Default")
      (node (ref "LOW-IN") (pin "3") (pinfunction "3_3") (pintype "passive"))
      (node (ref "RCB7") (pin "1") (pinfunction "1_1") (pintype "passive"))
    )
    (net (code "36") (name "/CB7-IN-1") (class "Default")
      (node (ref "HIGH-IN") (pin "3") (pinfunction "3_3") (pintype "passive"))
      (node (ref "RCB7-1") (pin "1") (pinfunction "1_1") (pintype "passive"))
    )
    (net (code "37") (name "/CB8") (class "Default")
      (node (ref "CCB8") (pin "1") (pinfunction "1_1") (pintype "passive"))
      (node (ref "CCB9") (pin "2") (pinfunction "2_2") (pintype "passive"))
      (node (ref "IC2") (pin "18") (pinfunction "CB8_18") (pintype "bidirectional"))
      (node (ref "RCB8") (pin "2") (pinfunction "2_2") (pintype "passive"))
    )
    (net (code "38") (name "/CB8-1") (class "Default")
      (node (ref "CCB8-1") (pin "1") (pinfunction "1_1") (pintype "passive"))
      (node (ref "CCB9-1") (pin "2") (pinfunction "2_2") (pintype "passive"))
      (node (ref "IC1") (pin "18") (pinfunction "CB8_18") (pintype "bidirectional"))
      (node (ref "RCB8-1") (pin "2") (pinfunction "2_2") (pintype "passive"))
    )
    (net (code "39") (name "/CB8-IN") (class "Default")
      (node (ref "LOW-IN") (pin "2") (pinfunction "2_2") (pintype "passive"))
      (node (ref "RCB8") (pin "1") (pinfunction "1_1") (pintype "passive"))
    )
    (net (code "40") (name "/CB8-IN-1") (class "Default")
      (node (ref "HIGH-IN") (pin "2") (pinfunction "2_2") (pintype "passive"))
      (node (ref "RCB8-1") (pin "1") (pinfunction "1_1") (pintype "passive"))
    )
    (net (code "41") (name "/CB9") (class "Default")
      (node (ref "CCB10") (pin "2") (pinfunction "2_2") (pintype "passive"))
      (node (ref "CCB9") (pin "1") (pinfunction "1_1") (pintype "passive"))
      (node (ref "IC2") (pin "16") (pinfunction "CB9_16") (pintype "bidirectional"))
      (node (ref "RCB9") (pin "2") (pinfunction "2_2") (pintype "passive"))
    )
    (net (code "42") (name "/CB9-1") (class "Default")
      (node (ref "CCB10-1") (pin "2") (pinfunction "2_2") (pintype "passive"))
      (node (ref "CCB9-1") (pin "1") (pinfunction "1_1") (pintype "passive"))
      (node (ref "IC1") (pin "16") (pinfunction "CB9_16") (pintype "bidirectional"))
      (node (ref "RCB9-1") (pin "2") (pinfunction "2_2") (pintype "passive"))
    )
    (net (code "43") (name "/COMHN") (class "Default")
      (node (ref "CBPH1") (pin "1") (pinfunction "1_1") (pintype "passive"))
      (node (ref "IC2") (pin "42") (pinfunction "COMHN_42") (pintype "bidirectional"))
      (node (ref "RCOMH1") (pin "2") (pinfunction "2_2") (pintype "passive"))
      (node (ref "RTERMH") (pin "1") (pinfunction "1_1") (pintype "passive"))
    )
    (net (code "44") (name "/COMHN-1") (class "Default")
      (node (ref "CCOMLN_BP-1") (pin "1") (pinfunction "1_1") (pintype "passive"))
      (node (ref "IC1") (pin "42") (pinfunction "COMHN_42") (pintype "bidirectional"))
      (node (ref "RCOMH1-1") (pin "2") (pinfunction "2_2") (pintype "passive"))
      (node (ref "RCOMML-1") (pin "1") (pinfunction "1_1") (pintype "passive"))
    )
    (net (code "45") (name "/COMHP") (class "Default")
      (node (ref "CBPH") (pin "1") (pinfunction "1_1") (pintype "passive"))
      (node (ref "IC2") (pin "43") (pinfunction "COMHP_43") (pintype "bidirectional"))
      (node (ref "RCOMH") (pin "2") (pinfunction "2_2") (pintype "passive"))
      (node (ref "RTERMH") (pin "2") (pinfunction "2_2") (pintype "passive"))
    )
    (net (code "46") (name "/COMHP-1") (class "Default")
      (node (ref "CCOMLP_BP-1") (pin "1") (pinfunction "1_1") (pintype "passive"))
      (node (ref "IC1") (pin "43") (pinfunction "COMHP_43") (pintype "bidirectional"))
      (node (ref "RCOMH-1") (pin "2") (pinfunction "2_2") (pintype "passive"))
      (node (ref "RCOMML-1") (pin "2") (pinfunction "2_2") (pintype "passive"))
    )
    (net (code "47") (name "/COMLN") (class "Default")
      (node (ref "CCOMLN_BP") (pin "1") (pinfunction "1_1") (pintype "passive"))
      (node (ref "IC2") (pin "41") (pinfunction "COMLN_41") (pintype "bidirectional"))
      (node (ref "RCOML1") (pin "2") (pinfunction "2_2") (pintype "passive"))
      (node (ref "RCOMML") (pin "2") (pinfunction "2_2") (pintype "passive"))
    )
    (net (code "48") (name "/COMLN-1") (class "Default")
      (node (ref "CBPL1") (pin "1") (pinfunction "1_1") (pintype "passive"))
      (node (ref "IC1") (pin "41") (pinfunction "COMLN_41") (pintype "bidirectional"))
      (node (ref "RCOML1-1") (pin "2") (pinfunction "2_2") (pintype "passive"))
      (node (ref "RTERML") (pin "2") (pinfunction "2_2") (pintype "passive"))
    )
    (net (code "49") (name "/COMLP") (class "Default")
      (node (ref "CCOMLP_BP") (pin "1") (pinfunction "1_1") (pintype "passive"))
      (node (ref "IC2") (pin "40") (pinfunction "COMLP_40") (pintype "bidirectional"))
      (node (ref "RCOML") (pin "2") (pinfunction "2_2") (pintype "passive"))
      (node (ref "RCOMML") (pin "1") (pinfunction "1_1") (pintype "passive"))
    )
    (net (code "50") (name "/COMLP-1") (class "Default")
      (node (ref "CBPL") (pin "1") (pinfunction "1_1") (pintype "passive"))
      (node (ref "IC1") (pin "40") (pinfunction "COMLP_40") (pintype "bidirectional"))
      (node (ref "RCOML-1") (pin "2") (pinfunction "2_2") (pintype "passive"))
      (node (ref "RTERML") (pin "1") (pinfunction "1_1") (pintype "passive"))
    )
    (net (code "51") (name "/CVDD") (class "Default")
      (node (ref "CCVDD") (pin "1") (pinfunction "1_1") (pintype "passive"))
      (node (ref "IC2") (pin "45") (pinfunction "CVDD_45") (pintype "bidirectional"))
      (node (ref "IC2") (pin "52") (pinfunction "RX_52") (pintype "bidirectional"))
    )
    (net (code "52") (name "/CVDD-1") (class "Default")
      (node (ref "CCVDD-1") (pin "1") (pinfunction "1_1") (pintype "passive"))
      (node (ref "IC1") (pin "45") (pinfunction "CVDD_45") (pintype "bidirectional"))
      (node (ref "IC1") (pin "52") (pinfunction "RX_52") (pintype "bidirectional"))
    )
    (net (code "53") (name "/DVDD") (class "Default")
      (node (ref "CDVDD") (pin "1") (pinfunction "1_1") (pintype "passive"))
      (node (ref "IC2") (pin "49") (pinfunction "DVDD_49") (pintype "bidirectional"))
    )
    (net (code "54") (name "/DVDD-1") (class "Default")
      (node (ref "CDVDD-1") (pin "1") (pinfunction "1_1") (pintype "passive"))
      (node (ref "IC1") (pin "49") (pinfunction "DVDD_49") (pintype "bidirectional"))
    )
    (net (code "55") (name "/GNDH") (class "Default")
      (node (ref "CAVDD-1") (pin "2") (pinfunction "2_2") (pintype "passive"))
      (node (ref "CBAT-1") (pin "1") (pinfunction "1_1") (pintype "passive"))
      (node (ref "CBPL") (pin "2") (pinfunction "2_2") (pintype "passive"))
      (node (ref "CBPL1") (pin "2") (pinfunction "2_2") (pintype "passive"))
      (node (ref "CCOMLN_BP-1") (pin "2") (pinfunction "2_2") (pintype "passive"))
      (node (ref "CCOMLP_BP-1") (pin "2") (pinfunction "2_2") (pintype "passive"))
      (node (ref "CCVDD-1") (pin "2") (pinfunction "2_2") (pintype "passive"))
      (node (ref "CDVDD-1") (pin "2") (pinfunction "2_2") (pintype "passive"))
      (node (ref "CLDOIN-1") (pin "2") (pinfunction "2_2") (pintype "passive"))
      (node (ref "CNEG5V-1") (pin "2") (pinfunction "2_2") (pintype "passive"))
      (node (ref "CNPN-1") (pin "1") (pinfunction "1_1") (pintype "passive"))
      (node (ref "CREFHP-1") (pin "2") (pinfunction "2_2") (pintype "passive"))
      (node (ref "CTEMP10") (pin "2") (pinfunction "2_2") (pintype "passive"))
      (node (ref "CTEMP11") (pin "2") (pinfunction "2_2") (pintype "passive"))
      (node (ref "CTEMP12") (pin "2") (pinfunction "2_2") (pintype "passive"))
      (node (ref "CTEMP13") (pin "2") (pinfunction "2_2") (pintype "passive"))
      (node (ref "CTEMP14") (pin "2") (pinfunction "2_2") (pintype "passive"))
      (node (ref "CTEMP15") (pin "2") (pinfunction "2_2") (pintype "passive"))
      (node (ref "CTEMP16") (pin "2") (pinfunction "2_2") (pintype "passive"))
      (node (ref "CTEMP9") (pin "2") (pinfunction "2_2") (pintype "passive"))
      (node (ref "CTSREF-1") (pin "2") (pinfunction "2_2") (pintype "passive"))
      (node (ref "CVC0-1") (pin "2") (pinfunction "2_2") (pintype "passive"))
      (node (ref "D2") (pin "3") (pinfunction "3_3") (pintype "bidirectional"))
      (node (ref "GNDH_PAD") (pin "1") (pinfunction "P_1") (pintype "passive"))
      (node (ref "HIGH-IN") (pin "15") (pinfunction "15_15") (pintype "passive"))
      (node (ref "HIGH-IN") (pin "25") (pinfunction "25_25") (pintype "passive"))
      (node (ref "HIGH-IN") (pin "30") (pinfunction "30_30") (pintype "passive"))
      (node (ref "IC1") (pin "36") (pinfunction "REFHM_36") (pintype "bidirectional"))
      (node (ref "IC1") (pin "39") (pinfunction "AVSS_39") (pintype "bidirectional"))
      (node (ref "IC1") (pin "46") (pinfunction "CVSS_46") (pintype "bidirectional"))
      (node (ref "IC1") (pin "50") (pinfunction "DVSS_50") (pintype "bidirectional"))
      (node (ref "IC1") (pin "65") (pinfunction "AVSS?_65") (pintype "bidirectional"))
      (node (ref "RVC0-1") (pin "1") (pinfunction "1_1") (pintype "passive"))
      (node (ref "TP4") (pin "TP") (pinfunction "TP_TP") (pintype "passive"))
    )
    (net (code "56") (name "/GNDL") (class "Default")
      (node (ref "CAVDD") (pin "2") (pinfunction "2_2") (pintype "passive"))
      (node (ref "CBAT") (pin "1") (pinfunction "1_1") (pintype "passive"))
      (node (ref "CBPH") (pin "2") (pinfunction "2_2") (pintype "passive"))
      (node (ref "CBPH1") (pin "2") (pinfunction "2_2") (pintype "passive"))
      (node (ref "CCOMLN_BP") (pin "2") (pinfunction "2_2") (pintype "passive"))
      (node (ref "CCOMLP_BP") (pin "2") (pinfunction "2_2") (pintype "passive"))
      (node (ref "CCVDD") (pin "2") (pinfunction "2_2") (pintype "passive"))
      (node (ref "CDVDD") (pin "2") (pinfunction "2_2") (pintype "passive"))
      (node (ref "CLDOIN") (pin "2") (pinfunction "2_2") (pintype "passive"))
      (node (ref "CNEG5V") (pin "2") (pinfunction "2_2") (pintype "passive"))
      (node (ref "CNPN") (pin "1") (pinfunction "1_1") (pintype "passive"))
      (node (ref "CREFHP") (pin "2") (pinfunction "2_2") (pintype "passive"))
      (node (ref "CTEMP1") (pin "2") (pinfunction "2_2") (pintype "passive"))
      (node (ref "CTEMP2") (pin "2") (pinfunction "2_2") (pintype "passive"))
      (node (ref "CTEMP3") (pin "2") (pinfunction "2_2") (pintype "passive"))
      (node (ref "CTEMP4") (pin "2") (pinfunction "2_2") (pintype "passive"))
      (node (ref "CTEMP5") (pin "2") (pinfunction "2_2") (pintype "passive"))
      (node (ref "CTEMP6") (pin "2") (pinfunction "2_2") (pintype "passive"))
      (node (ref "CTEMP7") (pin "2") (pinfunction "2_2") (pintype "passive"))
      (node (ref "CTEMP8") (pin "2") (pinfunction "2_2") (pintype "passive"))
      (node (ref "CTSREF") (pin "2") (pinfunction "2_2") (pintype "passive"))
      (node (ref "CVC0") (pin "2") (pinfunction "2_2") (pintype "passive"))
      (node (ref "D1") (pin "3") (pinfunction "3_3") (pintype "bidirectional"))
      (node (ref "GNDL_PAD") (pin "1") (pinfunction "P_1") (pintype "passive"))
      (node (ref "IC2") (pin "36") (pinfunction "REFHM_36") (pintype "bidirectional"))
      (node (ref "IC2") (pin "39") (pinfunction "AVSS_39") (pintype "bidirectional"))
      (node (ref "IC2") (pin "46") (pinfunction "CVSS_46") (pintype "bidirectional"))
      (node (ref "IC2") (pin "50") (pinfunction "DVSS_50") (pintype "bidirectional"))
      (node (ref "IC2") (pin "65") (pinfunction "AVSS?_65") (pintype "bidirectional"))
      (node (ref "LOW-IN") (pin "15") (pinfunction "15_15") (pintype "passive"))
      (node (ref "LOW-IN") (pin "25") (pinfunction "25_25") (pintype "passive"))
      (node (ref "LOW-IN") (pin "30") (pinfunction "30_30") (pintype "passive"))
      (node (ref "RVC0") (pin "1") (pinfunction "1_1") (pintype "passive"))
      (node (ref "TP2") (pin "TP") (pinfunction "TP_TP") (pintype "passive"))
    )
    (net (code "57") (name "/ISO_COMN") (class "Default")
      (node (ref "C4") (pin "2") (pinfunction "B_2") (pintype "passive"))
      (node (ref "RCOML1-1") (pin "1") (pinfunction "1_1") (pintype "passive"))
    )
    (net (code "58") (name "/ISO_COMP") (class "Default")
      (node (ref "C3") (pin "2") (pinfunction "B_2") (pintype "passive"))
      (node (ref "RCOML-1") (pin "1") (pinfunction "1_1") (pintype "passive"))
    )
    (net (code "59") (name "/LDOIN") (class "Default")
      (node (ref "CLDOIN") (pin "1") (pinfunction "1_1") (pintype "passive"))
      (node (ref "IC2") (pin "47") (pinfunction "LDOIN_47") (pintype "bidirectional"))
      (node (ref "T1") (pin "E") (pinfunction "E_E") (pintype "passive"))
    )
    (net (code "60") (name "/LDOIN-1") (class "Default")
      (node (ref "CLDOIN-1") (pin "1") (pinfunction "1_1") (pintype "passive"))
      (node (ref "IC1") (pin "47") (pinfunction "LDOIN_47") (pintype "bidirectional"))
      (node (ref "T2") (pin "E") (pinfunction "E_E") (pintype "passive"))
    )
    (net (code "61") (name "/NOT_USED_VC_CB") (class "Default")
      (node (ref "CBAT") (pin "2") (pinfunction "2_2") (pintype "passive"))
      (node (ref "CCB10") (pin "1") (pinfunction "1_1") (pintype "passive"))
      (node (ref "IC2") (pin "1") (pinfunction "BAT_1") (pintype "bidirectional"))
      (node (ref "IC2") (pin "10") (pinfunction "CB12_10") (pintype "bidirectional"))
      (node (ref "IC2") (pin "11") (pinfunction "VC12_11") (pintype "bidirectional"))
      (node (ref "IC2") (pin "12") (pinfunction "CB11_12") (pintype "bidirectional"))
      (node (ref "IC2") (pin "13") (pinfunction "VC11_13") (pintype "bidirectional"))
      (node (ref "IC2") (pin "14") (pinfunction "CB10_14") (pintype "bidirectional"))
      (node (ref "IC2") (pin "15") (pinfunction "VC10_15") (pintype "bidirectional"))
      (node (ref "IC2") (pin "2") (pinfunction "CB16_2") (pintype "bidirectional"))
      (node (ref "IC2") (pin "3") (pinfunction "VC16_3") (pintype "bidirectional"))
      (node (ref "IC2") (pin "4") (pinfunction "CB15_4") (pintype "bidirectional"))
      (node (ref "IC2") (pin "5") (pinfunction "VC15_5") (pintype "bidirectional"))
      (node (ref "IC2") (pin "6") (pinfunction "CB14_6") (pintype "bidirectional"))
      (node (ref "IC2") (pin "7") (pinfunction "VC14_7") (pintype "bidirectional"))
      (node (ref "IC2") (pin "8") (pinfunction "CB13_8") (pintype "bidirectional"))
      (node (ref "IC2") (pin "9") (pinfunction "VC13_9") (pintype "bidirectional"))
      (node (ref "RBAT") (pin "2") (pinfunction "2_2") (pintype "passive"))
    )
    (net (code "62") (name "/NOT_USED_VC_CB_HIGH") (class "Default")
      (node (ref "CBAT-1") (pin "2") (pinfunction "2_2") (pintype "passive"))
      (node (ref "CCB10-1") (pin "1") (pinfunction "1_1") (pintype "passive"))
      (node (ref "IC1") (pin "1") (pinfunction "BAT_1") (pintype "bidirectional"))
      (node (ref "IC1") (pin "10") (pinfunction "CB12_10") (pintype "bidirectional"))
      (node (ref "IC1") (pin "11") (pinfunction "VC12_11") (pintype "bidirectional"))
      (node (ref "IC1") (pin "12") (pinfunction "CB11_12") (pintype "bidirectional"))
      (node (ref "IC1") (pin "13") (pinfunction "VC11_13") (pintype "bidirectional"))
      (node (ref "IC1") (pin "14") (pinfunction "CB10_14") (pintype "bidirectional"))
      (node (ref "IC1") (pin "15") (pinfunction "VC10_15") (pintype "bidirectional"))
      (node (ref "IC1") (pin "2") (pinfunction "CB16_2") (pintype "bidirectional"))
      (node (ref "IC1") (pin "3") (pinfunction "VC16_3") (pintype "bidirectional"))
      (node (ref "IC1") (pin "4") (pinfunction "CB15_4") (pintype "bidirectional"))
      (node (ref "IC1") (pin "5") (pinfunction "VC15_5") (pintype "bidirectional"))
      (node (ref "IC1") (pin "6") (pinfunction "CB14_6") (pintype "bidirectional"))
      (node (ref "IC1") (pin "7") (pinfunction "VC14_7") (pintype "bidirectional"))
      (node (ref "IC1") (pin "8") (pinfunction "CB13_8") (pintype "bidirectional"))
      (node (ref "IC1") (pin "9") (pinfunction "VC13_9") (pintype "bidirectional"))
      (node (ref "RBAT-1") (pin "2") (pinfunction "2_2") (pintype "passive"))
    )
    (net (code "63") (name "/NPNB") (class "Default")
      (node (ref "IC2") (pin "48") (pinfunction "NPNB_48") (pintype "bidirectional"))
      (node (ref "T1") (pin "B") (pinfunction "B_B") (pintype "passive"))
    )
    (net (code "64") (name "/NPNB-1") (class "Default")
      (node (ref "IC1") (pin "48") (pinfunction "NPNB_48") (pintype "bidirectional"))
      (node (ref "T2") (pin "B") (pinfunction "B_B") (pintype "passive"))
    )
    (net (code "65") (name "/REFHP") (class "Default")
      (node (ref "CREFHP") (pin "1") (pinfunction "1_1") (pintype "passive"))
      (node (ref "IC2") (pin "37") (pinfunction "REFHP_37") (pintype "bidirectional"))
    )
    (net (code "66") (name "/REFHP-1") (class "Default")
      (node (ref "CREFHP-1") (pin "1") (pinfunction "1_1") (pintype "passive"))
      (node (ref "IC1") (pin "37") (pinfunction "REFHP_37") (pintype "bidirectional"))
    )
    (net (code "67") (name "/SRN") (class "Default")
      (node (ref "CCS") (pin "1") (pinfunction "1_1") (pintype "passive"))
      (node (ref "IC2") (pin "63") (pinfunction "BBN(SRN)_63") (pintype "bidirectional"))
      (node (ref "RCS2") (pin "1") (pinfunction "1_1") (pintype "passive"))
    )
    (net (code "68") (name "/SRN-IN") (class "Default")
      (node (ref "RCS2") (pin "2") (pinfunction "2_2") (pintype "passive"))
      (node (ref "SR") (pin "3") (pinfunction "3_3") (pintype "passive"))
    )
    (net (code "69") (name "/SRP") (class "Default")
      (node (ref "CCS") (pin "2") (pinfunction "2_2") (pintype "passive"))
      (node (ref "IC2") (pin "64") (pinfunction "BBP(SRP)_64") (pintype "bidirectional"))
      (node (ref "RCS1") (pin "1") (pinfunction "1_1") (pintype "passive"))
    )
    (net (code "70") (name "/SRP-IN") (class "Default")
      (node (ref "RCS1") (pin "2") (pinfunction "2_2") (pintype "passive"))
      (node (ref "SR") (pin "4") (pinfunction "4_4") (pintype "passive"))
    )
    (net (code "71") (name "/TEMP1") (class "Default")
      (node (ref "CTEMP1") (pin "1") (pinfunction "1_1") (pintype "passive"))
      (node (ref "IC2") (pin "61") (pinfunction "GPIO1_61") (pintype "bidirectional"))
      (node (ref "LOW-IN") (pin "26") (pinfunction "26_26") (pintype "passive"))
      (node (ref "RTHRM1") (pin "2") (pinfunction "2_2") (pintype "passive"))
    )
    (net (code "72") (name "/TEMP2") (class "Default")
      (node (ref "CTEMP2") (pin "1") (pinfunction "1_1") (pintype "passive"))
      (node (ref "IC2") (pin "60") (pinfunction "GPIO2_60") (pintype "bidirectional"))
      (node (ref "LOW-IN") (pin "11") (pinfunction "11_11") (pintype "passive"))
      (node (ref "RTHRM2") (pin "2") (pinfunction "2_2") (pintype "passive"))
    )
    (net (code "73") (name "/TEMP3") (class "Default")
      (node (ref "CTEMP3") (pin "1") (pinfunction "1_1") (pintype "passive"))
      (node (ref "IC2") (pin "59") (pinfunction "GPIO3_59") (pintype "bidirectional"))
      (node (ref "LOW-IN") (pin "27") (pinfunction "27_27") (pintype "passive"))
      (node (ref "RTHRM3") (pin "2") (pinfunction "2_2") (pintype "passive"))
    )
    (net (code "74") (name "/TEMP4") (class "Default")
      (node (ref "CTEMP4") (pin "1") (pinfunction "1_1") (pintype "passive"))
      (node (ref "IC2") (pin "58") (pinfunction "GPIO4_58") (pintype "bidirectional"))
      (node (ref "LOW-IN") (pin "12") (pinfunction "12_12") (pintype "passive"))
      (node (ref "RTHRM4") (pin "2") (pinfunction "2_2") (pintype "passive"))
    )
    (net (code "75") (name "/TEMP5") (class "Default")
      (node (ref "CTEMP5") (pin "1") (pinfunction "1_1") (pintype "passive"))
      (node (ref "IC2") (pin "57") (pinfunction "GPIO5_57") (pintype "bidirectional"))
      (node (ref "LOW-IN") (pin "28") (pinfunction "28_28") (pintype "passive"))
      (node (ref "RTHRM5") (pin "2") (pinfunction "2_2") (pintype "passive"))
    )
    (net (code "76") (name "/TEMP6") (class "Default")
      (node (ref "CTEMP6") (pin "1") (pinfunction "1_1") (pintype "passive"))
      (node (ref "IC2") (pin "56") (pinfunction "GPIO6_56") (pintype "bidirectional"))
      (node (ref "LOW-IN") (pin "13") (pinfunction "13_13") (pintype "passive"))
      (node (ref "RTHRM6") (pin "2") (pinfunction "2_2") (pintype "passive"))
    )
    (net (code "77") (name "/TEMP7") (class "Default")
      (node (ref "CTEMP7") (pin "1") (pinfunction "1_1") (pintype "passive"))
      (node (ref "IC2") (pin "55") (pinfunction "GPIO7_55") (pintype "bidirectional"))
      (node (ref "LOW-IN") (pin "29") (pinfunction "29_29") (pintype "passive"))
      (node (ref "RTHRM7") (pin "2") (pinfunction "2_2") (pintype "passive"))
    )
    (net (code "78") (name "/TEMP8") (class "Default")
      (node (ref "CTEMP8") (pin "1") (pinfunction "1_1") (pintype "passive"))
      (node (ref "IC2") (pin "54") (pinfunction "GPIO8_54") (pintype "bidirectional"))
      (node (ref "LOW-IN") (pin "14") (pinfunction "14_14") (pintype "passive"))
      (node (ref "RTHRM8") (pin "2") (pinfunction "2_2") (pintype "passive"))
    )
    (net (code "79") (name "/TEMP9") (class "Default")
      (node (ref "CTEMP9") (pin "1") (pinfunction "1_1") (pintype "passive"))
      (node (ref "HIGH-IN") (pin "26") (pinfunction "26_26") (pintype "passive"))
      (node (ref "IC1") (pin "61") (pinfunction "GPIO1_61") (pintype "bidirectional"))
      (node (ref "RTHRM1-1") (pin "2") (pinfunction "2_2") (pintype "passive"))
    )
    (net (code "80") (name "/TEMP10") (class "Default")
      (node (ref "CTEMP10") (pin "1") (pinfunction "1_1") (pintype "passive"))
      (node (ref "HIGH-IN") (pin "11") (pinfunction "11_11") (pintype "passive"))
      (node (ref "IC1") (pin "60") (pinfunction "GPIO2_60") (pintype "bidirectional"))
      (node (ref "RTHRM2-1") (pin "2") (pinfunction "2_2") (pintype "passive"))
    )
    (net (code "81") (name "/TEMP11") (class "Default")
      (node (ref "CTEMP11") (pin "1") (pinfunction "1_1") (pintype "passive"))
      (node (ref "HIGH-IN") (pin "27") (pinfunction "27_27") (pintype "passive"))
      (node (ref "IC1") (pin "59") (pinfunction "GPIO3_59") (pintype "bidirectional"))
      (node (ref "RTHRM3-1") (pin "2") (pinfunction "2_2") (pintype "passive"))
    )
    (net (code "82") (name "/TEMP12") (class "Default")
      (node (ref "CTEMP12") (pin "1") (pinfunction "1_1") (pintype "passive"))
      (node (ref "HIGH-IN") (pin "12") (pinfunction "12_12") (pintype "passive"))
      (node (ref "IC1") (pin "58") (pinfunction "GPIO4_58") (pintype "bidirectional"))
      (node (ref "RTHRM4-1") (pin "2") (pinfunction "2_2") (pintype "passive"))
    )
    (net (code "83") (name "/TEMP13") (class "Default")
      (node (ref "CTEMP13") (pin "1") (pinfunction "1_1") (pintype "passive"))
      (node (ref "HIGH-IN") (pin "28") (pinfunction "28_28") (pintype "passive"))
      (node (ref "IC1") (pin "57") (pinfunction "GPIO5_57") (pintype "bidirectional"))
      (node (ref "RTHRM5-1") (pin "2") (pinfunction "2_2") (pintype "passive"))
    )
    (net (code "84") (name "/TEMP14") (class "Default")
      (node (ref "CTEMP14") (pin "1") (pinfunction "1_1") (pintype "passive"))
      (node (ref "HIGH-IN") (pin "13") (pinfunction "13_13") (pintype "passive"))
      (node (ref "IC1") (pin "56") (pinfunction "GPIO6_56") (pintype "bidirectional"))
      (node (ref "RTHRM6-1") (pin "2") (pinfunction "2_2") (pintype "passive"))
    )
    (net (code "85") (name "/TEMP15") (class "Default")
      (node (ref "CTEMP15") (pin "1") (pinfunction "1_1") (pintype "passive"))
      (node (ref "HIGH-IN") (pin "29") (pinfunction "29_29") (pintype "passive"))
      (node (ref "IC1") (pin "55") (pinfunction "GPIO7_55") (pintype "bidirectional"))
      (node (ref "RTHRM7-1") (pin "2") (pinfunction "2_2") (pintype "passive"))
    )
    (net (code "86") (name "/TEMP16") (class "Default")
      (node (ref "CTEMP16") (pin "1") (pinfunction "1_1") (pintype "passive"))
      (node (ref "HIGH-IN") (pin "14") (pinfunction "14_14") (pintype "passive"))
      (node (ref "IC1") (pin "54") (pinfunction "GPIO8_54") (pintype "bidirectional"))
      (node (ref "RTHRM8-1") (pin "2") (pinfunction "2_2") (pintype "passive"))
    )
    (net (code "87") (name "/TP") (class "Default")
      (node (ref "IC2") (pin "62") (pinfunction "NFAULT_62") (pintype "bidirectional"))
      (node (ref "TP3") (pin "TP") (pinfunction "TP_TP") (pintype "passive"))
      (node (ref "TP_NFAUL") (pin "TP") (pinfunction "TP_TP") (pintype "input"))
    )
    (net (code "88") (name "/TP-1") (class "Default")
      (node (ref "IC1") (pin "62") (pinfunction "NFAULT_62") (pintype "bidirectional"))
      (node (ref "TP1") (pin "TP") (pinfunction "TP_TP") (pintype "passive"))
      (node (ref "TP_NFAUL-1") (pin "TP") (pinfunction "TP_TP") (pintype "input"))
    )
    (net (code "89") (name "/TSREF") (class "Default")
      (node (ref "CTSREF") (pin "1") (pinfunction "1_1") (pintype "passive"))
      (node (ref "IC2") (pin "51") (pinfunction "TSREF_51") (pintype "bidirectional"))
      (node (ref "RTHRM1") (pin "1") (pinfunction "1_1") (pintype "passive"))
      (node (ref "RTHRM2") (pin "1") (pinfunction "1_1") (pintype "passive"))
      (node (ref "RTHRM3") (pin "1") (pinfunction "1_1") (pintype "passive"))
      (node (ref "RTHRM4") (pin "1") (pinfunction "1_1") (pintype "passive"))
      (node (ref "RTHRM5") (pin "1") (pinfunction "1_1") (pintype "passive"))
      (node (ref "RTHRM6") (pin "1") (pinfunction "1_1") (pintype "passive"))
      (node (ref "RTHRM7") (pin "1") (pinfunction "1_1") (pintype "passive"))
      (node (ref "RTHRM8") (pin "1") (pinfunction "1_1") (pintype "passive"))
    )
    (net (code "90") (name "/TSREF-1") (class "Default")
      (node (ref "CTSREF-1") (pin "1") (pinfunction "1_1") (pintype "passive"))
      (node (ref "IC1") (pin "51") (pinfunction "TSREF_51") (pintype "bidirectional"))
      (node (ref "RTHRM1-1") (pin "1") (pinfunction "1_1") (pintype "passive"))
      (node (ref "RTHRM2-1") (pin "1") (pinfunction "1_1") (pintype "passive"))
      (node (ref "RTHRM3-1") (pin "1") (pinfunction "1_1") (pintype "passive"))
      (node (ref "RTHRM4-1") (pin "1") (pinfunction "1_1") (pintype "passive"))
      (node (ref "RTHRM5-1") (pin "1") (pinfunction "1_1") (pintype "passive"))
      (node (ref "RTHRM6-1") (pin "1") (pinfunction "1_1") (pintype "passive"))
      (node (ref "RTHRM7-1") (pin "1") (pinfunction "1_1") (pintype "passive"))
      (node (ref "RTHRM8-1") (pin "1") (pinfunction "1_1") (pintype "passive"))
    )
    (net (code "91") (name "/VC0") (class "Default")
      (node (ref "CVC0") (pin "1") (pinfunction "1_1") (pintype "passive"))
      (node (ref "CVC1") (pin "2") (pinfunction "2_2") (pintype "passive"))
      (node (ref "IC2") (pin "35") (pinfunction "VC0_35") (pintype "bidirectional"))
      (node (ref "RVC0") (pin "2") (pinfunction "2_2") (pintype "passive"))
    )
    (net (code "92") (name "/VC0-1") (class "Default")
      (node (ref "CVC0-1") (pin "1") (pinfunction "1_1") (pintype "passive"))
      (node (ref "CVC1-1") (pin "2") (pinfunction "2_2") (pintype "passive"))
      (node (ref "IC1") (pin "35") (pinfunction "VC0_35") (pintype "bidirectional"))
      (node (ref "RVC0-1") (pin "2") (pinfunction "2_2") (pintype "passive"))
    )
    (net (code "93") (name "/VC1") (class "Default")
      (node (ref "CVC1") (pin "1") (pinfunction "1_1") (pintype "passive"))
      (node (ref "CVC2") (pin "2") (pinfunction "2_2") (pintype "passive"))
      (node (ref "IC2") (pin "33") (pinfunction "VC1_33") (pintype "bidirectional"))
      (node (ref "RVC1") (pin "2") (pinfunction "2_2") (pintype "passive"))
    )
    (net (code "94") (name "/VC1-1") (class "Default")
      (node (ref "CVC1-1") (pin "1") (pinfunction "1_1") (pintype "passive"))
      (node (ref "CVC2-1") (pin "2") (pinfunction "2_2") (pintype "passive"))
      (node (ref "IC1") (pin "33") (pinfunction "VC1_33") (pintype "bidirectional"))
      (node (ref "RVC1-1") (pin "2") (pinfunction "2_2") (pintype "passive"))
    )
    (net (code "95") (name "/VC1-IN") (class "Default")
      (node (ref "LOW-IN") (pin "24") (pinfunction "24_24") (pintype "passive"))
      (node (ref "RVC1") (pin "1") (pinfunction "1_1") (pintype "passive"))
    )
    (net (code "96") (name "/VC1-IN-1") (class "Default")
      (node (ref "HIGH-IN") (pin "24") (pinfunction "24_24") (pintype "passive"))
      (node (ref "RVC1-1") (pin "1") (pinfunction "1_1") (pintype "passive"))
    )
    (net (code "97") (name "/VC2") (class "Default")
      (node (ref "CVC2") (pin "1") (pinfunction "1_1") (pintype "passive"))
      (node (ref "CVC3") (pin "2") (pinfunction "2_2") (pintype "passive"))
      (node (ref "IC2") (pin "31") (pinfunction "VC2_31") (pintype "bidirectional"))
      (node (ref "RVC2") (pin "2") (pinfunction "2_2") (pintype "passive"))
    )
    (net (code "98") (name "/VC2-1") (class "Default")
      (node (ref "CVC2-1") (pin "1") (pinfunction "1_1") (pintype "passive"))
      (node (ref "CVC3-1") (pin "2") (pinfunction "2_2") (pintype "passive"))
      (node (ref "IC1") (pin "31") (pinfunction "VC2_31") (pintype "bidirectional"))
      (node (ref "RVC2-1") (pin "2") (pinfunction "2_2") (pintype "passive"))
    )
    (net (code "99") (name "/VC2-IN") (class "Default")
      (node (ref "LOW-IN") (pin "23") (pinfunction "23_23") (pintype "passive"))
      (node (ref "RVC2") (pin "1") (pinfunction "1_1") (pintype "passive"))
    )
    (net (code "100") (name "/VC2-IN-1") (class "Default")
      (node (ref "HIGH-IN") (pin "23") (pinfunction "23_23") (pintype "passive"))
      (node (ref "RVC2-1") (pin "1") (pinfunction "1_1") (pintype "passive"))
    )
    (net (code "101") (name "/VC3") (class "Default")
      (node (ref "CVC3") (pin "1") (pinfunction "1_1") (pintype "passive"))
      (node (ref "CVC4") (pin "2") (pinfunction "2_2") (pintype "passive"))
      (node (ref "IC2") (pin "29") (pinfunction "VC3_29") (pintype "bidirectional"))
      (node (ref "RVC3") (pin "2") (pinfunction "2_2") (pintype "passive"))
    )
    (net (code "102") (name "/VC3-1") (class "Default")
      (node (ref "CVC3-1") (pin "1") (pinfunction "1_1") (pintype "passive"))
      (node (ref "CVC4-1") (pin "2") (pinfunction "2_2") (pintype "passive"))
      (node (ref "IC1") (pin "29") (pinfunction "VC3_29") (pintype "bidirectional"))
      (node (ref "RVC3-1") (pin "2") (pinfunction "2_2") (pintype "passive"))
    )
    (net (code "103") (name "/VC3-IN") (class "Default")
      (node (ref "LOW-IN") (pin "22") (pinfunction "22_22") (pintype "passive"))
      (node (ref "RVC3") (pin "1") (pinfunction "1_1") (pintype "passive"))
    )
    (net (code "104") (name "/VC3-IN-1") (class "Default")
      (node (ref "HIGH-IN") (pin "22") (pinfunction "22_22") (pintype "passive"))
      (node (ref "RVC3-1") (pin "1") (pinfunction "1_1") (pintype "passive"))
    )
    (net (code "105") (name "/VC4") (class "Default")
      (node (ref "CVC4") (pin "1") (pinfunction "1_1") (pintype "passive"))
      (node (ref "CVC5") (pin "2") (pinfunction "2_2") (pintype "passive"))
      (node (ref "IC2") (pin "27") (pinfunction "VC4_27") (pintype "bidirectional"))
      (node (ref "RCV4") (pin "2") (pinfunction "2_2") (pintype "passive"))
    )
    (net (code "106") (name "/VC4-1") (class "Default")
      (node (ref "CVC4-1") (pin "1") (pinfunction "1_1") (pintype "passive"))
      (node (ref "CVC5-1") (pin "2") (pinfunction "2_2") (pintype "passive"))
      (node (ref "IC1") (pin "27") (pinfunction "VC4_27") (pintype "bidirectional"))
      (node (ref "RCV4-1") (pin "2") (pinfunction "2_2") (pintype "passive"))
    )
    (net (code "107") (name "/VC4-IN") (class "Default")
      (node (ref "LOW-IN") (pin "21") (pinfunction "21_21") (pintype "passive"))
      (node (ref "RCV4") (pin "1") (pinfunction "1_1") (pintype "passive"))
    )
    (net (code "108") (name "/VC4-IN-1") (class "Default")
      (node (ref "HIGH-IN") (pin "21") (pinfunction "21_21") (pintype "passive"))
      (node (ref "RCV4-1") (pin "1") (pinfunction "1_1") (pintype "passive"))
    )
    (net (code "109") (name "/VC5") (class "Default")
      (node (ref "CVC5") (pin "1") (pinfunction "1_1") (pintype "passive"))
      (node (ref "CVC6") (pin "2") (pinfunction "2_2") (pintype "passive"))
      (node (ref "IC2") (pin "25") (pinfunction "VC5_25") (pintype "bidirectional"))
      (node (ref "RVC5") (pin "2") (pinfunction "2_2") (pintype "passive"))
    )
    (net (code "110") (name "/VC5-1") (class "Default")
      (node (ref "CVC5-1") (pin "1") (pinfunction "1_1") (pintype "passive"))
      (node (ref "CVC6-1") (pin "2") (pinfunction "2_2") (pintype "passive"))
      (node (ref "IC1") (pin "25") (pinfunction "VC5_25") (pintype "bidirectional"))
      (node (ref "RVC5-1") (pin "2") (pinfunction "2_2") (pintype "passive"))
    )
    (net (code "111") (name "/VC5-IN") (class "Default")
      (node (ref "LOW-IN") (pin "20") (pinfunction "20_20") (pintype "passive"))
      (node (ref "RVC5") (pin "1") (pinfunction "1_1") (pintype "passive"))
    )
    (net (code "112") (name "/VC5-IN-1") (class "Default")
      (node (ref "HIGH-IN") (pin "20") (pinfunction "20_20") (pintype "passive"))
      (node (ref "RVC5-1") (pin "1") (pinfunction "1_1") (pintype "passive"))
    )
    (net (code "113") (name "/VC6") (class "Default")
      (node (ref "CVC6") (pin "1") (pinfunction "1_1") (pintype "passive"))
      (node (ref "CVC7") (pin "2") (pinfunction "2_2") (pintype "passive"))
      (node (ref "IC2") (pin "23") (pinfunction "VC6_23") (pintype "bidirectional"))
      (node (ref "RVC6") (pin "2") (pinfunction "2_2") (pintype "passive"))
    )
    (net (code "114") (name "/VC6-1") (class "Default")
      (node (ref "CVC6-1") (pin "1") (pinfunction "1_1") (pintype "passive"))
      (node (ref "CVC7-1") (pin "2") (pinfunction "2_2") (pintype "passive"))
      (node (ref "IC1") (pin "23") (pinfunction "VC6_23") (pintype "bidirectional"))
      (node (ref "RVC6-1") (pin "2") (pinfunction "2_2") (pintype "passive"))
    )
    (net (code "115") (name "/VC6-IN") (class "Default")
      (node (ref "LOW-IN") (pin "19") (pinfunction "19_19") (pintype "passive"))
      (node (ref "RVC6") (pin "1") (pinfunction "1_1") (pintype "passive"))
    )
    (net (code "116") (name "/VC6-IN-1") (class "Default")
      (node (ref "HIGH-IN") (pin "19") (pinfunction "19_19") (pintype "passive"))
      (node (ref "RVC6-1") (pin "1") (pinfunction "1_1") (pintype "passive"))
    )
    (net (code "117") (name "/VC7") (class "Default")
      (node (ref "CVC7") (pin "1") (pinfunction "1_1") (pintype "passive"))
      (node (ref "CVC8") (pin "2") (pinfunction "2_2") (pintype "passive"))
      (node (ref "IC2") (pin "21") (pinfunction "VC7_21") (pintype "bidirectional"))
      (node (ref "RCV7") (pin "2") (pinfunction "2_2") (pintype "passive"))
    )
    (net (code "118") (name "/VC7-1") (class "Default")
      (node (ref "CVC7-1") (pin "1") (pinfunction "1_1") (pintype "passive"))
      (node (ref "CVC8-1") (pin "2") (pinfunction "2_2") (pintype "passive"))
      (node (ref "IC1") (pin "21") (pinfunction "VC7_21") (pintype "bidirectional"))
      (node (ref "RCV7-1") (pin "2") (pinfunction "2_2") (pintype "passive"))
    )
    (net (code "119") (name "/VC7-IN") (class "Default")
      (node (ref "LOW-IN") (pin "18") (pinfunction "18_18") (pintype "passive"))
      (node (ref "RCV7") (pin "1") (pinfunction "1_1") (pintype "passive"))
    )
    (net (code "120") (name "/VC7-IN-1") (class "Default")
      (node (ref "HIGH-IN") (pin "18") (pinfunction "18_18") (pintype "passive"))
      (node (ref "RCV7-1") (pin "1") (pinfunction "1_1") (pintype "passive"))
    )
    (net (code "121") (name "/VC8") (class "Default")
      (node (ref "CVC8") (pin "1") (pinfunction "1_1") (pintype "passive"))
      (node (ref "CVC9") (pin "2") (pinfunction "2_2") (pintype "passive"))
      (node (ref "IC2") (pin "19") (pinfunction "VC8_19") (pintype "bidirectional"))
      (node (ref "RVC8") (pin "2") (pinfunction "2_2") (pintype "passive"))
    )
    (net (code "122") (name "/VC8-1") (class "Default")
      (node (ref "CVC8-1") (pin "1") (pinfunction "1_1") (pintype "passive"))
      (node (ref "CVC9-1") (pin "2") (pinfunction "2_2") (pintype "passive"))
      (node (ref "IC1") (pin "19") (pinfunction "VC8_19") (pintype "bidirectional"))
      (node (ref "RVC8-1") (pin "2") (pinfunction "2_2") (pintype "passive"))
    )
    (net (code "123") (name "/VC8-IN") (class "Default")
      (node (ref "LOW-IN") (pin "17") (pinfunction "17_17") (pintype "passive"))
      (node (ref "RVC8") (pin "1") (pinfunction "1_1") (pintype "passive"))
    )
    (net (code "124") (name "/VC8-IN-1") (class "Default")
      (node (ref "HIGH-IN") (pin "17") (pinfunction "17_17") (pintype "passive"))
      (node (ref "RVC8-1") (pin "1") (pinfunction "1_1") (pintype "passive"))
    )
    (net (code "125") (name "/VC9") (class "Default")
      (node (ref "CVC9") (pin "1") (pinfunction "1_1") (pintype "passive"))
      (node (ref "IC2") (pin "17") (pinfunction "VC9_17") (pintype "bidirectional"))
      (node (ref "RVC9") (pin "2") (pinfunction "2_2") (pintype "passive"))
    )
    (net (code "126") (name "/VC9-1") (class "Default")
      (node (ref "CVC9-1") (pin "1") (pinfunction "1_1") (pintype "passive"))
      (node (ref "IC1") (pin "17") (pinfunction "VC9_17") (pintype "bidirectional"))
      (node (ref "RVC9-1") (pin "2") (pinfunction "2_2") (pintype "passive"))
    )
    (net (code "127") (name "/VC9-IN") (class "Default")
      (node (ref "LOW-IN") (pin "16") (pinfunction "16_16") (pintype "passive"))
      (node (ref "RVC9") (pin "1") (pinfunction "1_1") (pintype "passive"))
    )
    (net (code "128") (name "/VC9-IN-1") (class "Default")
      (node (ref "HIGH-IN") (pin "16") (pinfunction "16_16") (pintype "passive"))
      (node (ref "RVC9-1") (pin "1") (pinfunction "1_1") (pintype "passive"))
    )
    (net (code "129") (name "Net-(C1-A)") (class "Default")
      (node (ref "C1") (pin "1") (pinfunction "A_1") (pintype "passive"))
      (node (ref "D2") (pin "1") (pinfunction "1_1") (pintype "bidirectional"))
      (node (ref "RCOMH-1") (pin "1") (pinfunction "1_1") (pintype "passive"))
    )
    (net (code "130") (name "Net-(C1-B)") (class "Default")
      (node (ref "C1") (pin "2") (pinfunction "B_2") (pintype "passive"))
      (node (ref "COMMH") (pin "2") (pinfunction "2_2") (pintype "passive"))
    )
    (net (code "131") (name "Net-(C2-A)") (class "Default")
      (node (ref "C2") (pin "1") (pinfunction "A_1") (pintype "passive"))
      (node (ref "D2") (pin "2") (pinfunction "2_2") (pintype "bidirectional"))
      (node (ref "RCOMH1-1") (pin "1") (pinfunction "1_1") (pintype "passive"))
    )
    (net (code "132") (name "Net-(C2-B)") (class "Default")
      (node (ref "C2") (pin "2") (pinfunction "B_2") (pintype "passive"))
      (node (ref "COMMH") (pin "4") (pinfunction "4_4") (pintype "passive"))
    )
    (net (code "133") (name "Net-(C3-A)") (class "Default")
      (node (ref "C3") (pin "1") (pinfunction "A_1") (pintype "passive"))
      (node (ref "RCOMH") (pin "1") (pinfunction "1_1") (pintype "passive"))
    )
    (net (code "134") (name "Net-(C4-A)") (class "Default")
      (node (ref "C4") (pin "1") (pinfunction "A_1") (pintype "passive"))
      (node (ref "RCOMH1") (pin "1") (pinfunction "1_1") (pintype "passive"))
    )
    (net (code "135") (name "Net-(C5-A)") (class "Default")
      (node (ref "C5") (pin "1") (pinfunction "A_1") (pintype "passive"))
      (node (ref "COMML") (pin "2") (pinfunction "2_2") (pintype "passive"))
    )
    (net (code "136") (name "Net-(C5-B)") (class "Default")
      (node (ref "C5") (pin "2") (pinfunction "B_2") (pintype "passive"))
      (node (ref "D1") (pin "1") (pinfunction "1_1") (pintype "bidirectional"))
      (node (ref "RCOML1") (pin "1") (pinfunction "1_1") (pintype "passive"))
    )
    (net (code "137") (name "Net-(C6-A)") (class "Default")
      (node (ref "C6") (pin "1") (pinfunction "A_1") (pintype "passive"))
      (node (ref "COMML") (pin "4") (pinfunction "4_4") (pintype "passive"))
    )
    (net (code "138") (name "Net-(C6-B)") (class "Default")
      (node (ref "C6") (pin "2") (pinfunction "B_2") (pintype "passive"))
      (node (ref "D1") (pin "2") (pinfunction "2_2") (pintype "bidirectional"))
      (node (ref "RCOML") (pin "1") (pinfunction "1_1") (pintype "passive"))
    )
    (net (code "139") (name "Net-(CNPN-1-Pad2)") (class "Default")
      (node (ref "CNPN-1") (pin "2") (pinfunction "2_2") (pintype "passive"))
      (node (ref "RNPN-1") (pin "2") (pinfunction "2_2") (pintype "passive"))
      (node (ref "T2") (pin "C") (pinfunction "C_C") (pintype "passive"))
    )
    (net (code "140") (name "Net-(CNPN-Pad2)") (class "Default")
      (node (ref "CNPN") (pin "2") (pinfunction "2_2") (pintype "passive"))
      (node (ref "RNPN") (pin "2") (pinfunction "2_2") (pintype "passive"))
      (node (ref "T1") (pin "C") (pinfunction "C_C") (pintype "passive"))
    )
    (net (code "141") (name "Net-(IC1-NEG5V)") (class "Default")
      (node (ref "CNEG5V-1") (pin "1") (pinfunction "1_1") (pintype "passive"))
      (node (ref "IC1") (pin "44") (pinfunction "NEG5V_44") (pintype "bidirectional"))
    )
    (net (code "142") (name "Net-(IC2-NEG5V)") (class "Default")
      (node (ref "CNEG5V") (pin "1") (pinfunction "1_1") (pintype "passive"))
      (node (ref "IC2") (pin "44") (pinfunction "NEG5V_44") (pintype "bidirectional"))
    )
    (net (code "143") (name "unconnected-(COMMH-Pad1)") (class "Default")
      (node (ref "COMMH") (pin "1") (pinfunction "1_1") (pintype "passive"))
    )
    (net (code "144") (name "unconnected-(COMMH-Pad3)") (class "Default")
      (node (ref "COMMH") (pin "3") (pinfunction "3_3") (pintype "passive"))
    )
    (net (code "145") (name "unconnected-(COMML-Pad1)") (class "Default")
      (node (ref "COMML") (pin "1") (pinfunction "1_1") (pintype "passive"))
    )
    (net (code "146") (name "unconnected-(COMML-Pad3)") (class "Default")
      (node (ref "COMML") (pin "3") (pinfunction "3_3") (pintype "passive"))
    )
    (net (code "147") (name "unconnected-(IC1-BBN(SRN)-Pad63)") (class "Default")
      (node (ref "IC1") (pin "63") (pinfunction "BBN(SRN)_63") (pintype "bidirectional"))
    )
    (net (code "148") (name "unconnected-(IC1-BBP(SRP)-Pad64)") (class "Default")
      (node (ref "IC1") (pin "64") (pinfunction "BBP(SRP)_64") (pintype "bidirectional"))
    )
    (net (code "149") (name "unconnected-(IC1-TX-Pad53)") (class "Default")
      (node (ref "IC1") (pin "53") (pinfunction "TX_53") (pintype "bidirectional"))
    )
    (net (code "150") (name "unconnected-(IC2-TX-Pad53)") (class "Default")
      (node (ref "IC2") (pin "53") (pinfunction "TX_53") (pintype "bidirectional"))
    )
    (net (code "151") (name "unconnected-(SR-Pad1)") (class "Default")
      (node (ref "SR") (pin "1") (pinfunction "1_1") (pintype "passive"))
    )
    (net (code "152") (name "unconnected-(SR-Pad2)") (class "Default")
      (node (ref "SR") (pin "2") (pinfunction "2_2") (pintype "passive"))
    )
  )
)
